# gyrotestbench.net
KiCad netlist of a schematic drawn in EAGLE
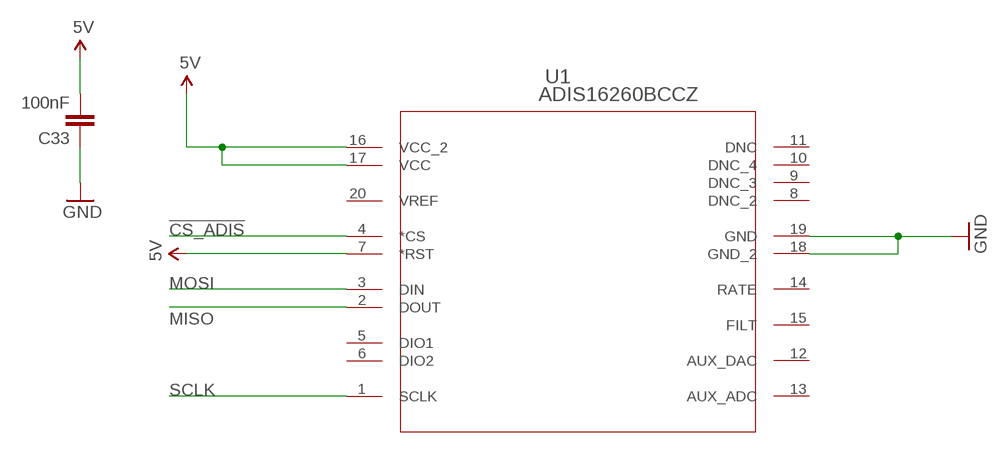
[diagram p0: schematic, sheet 1]
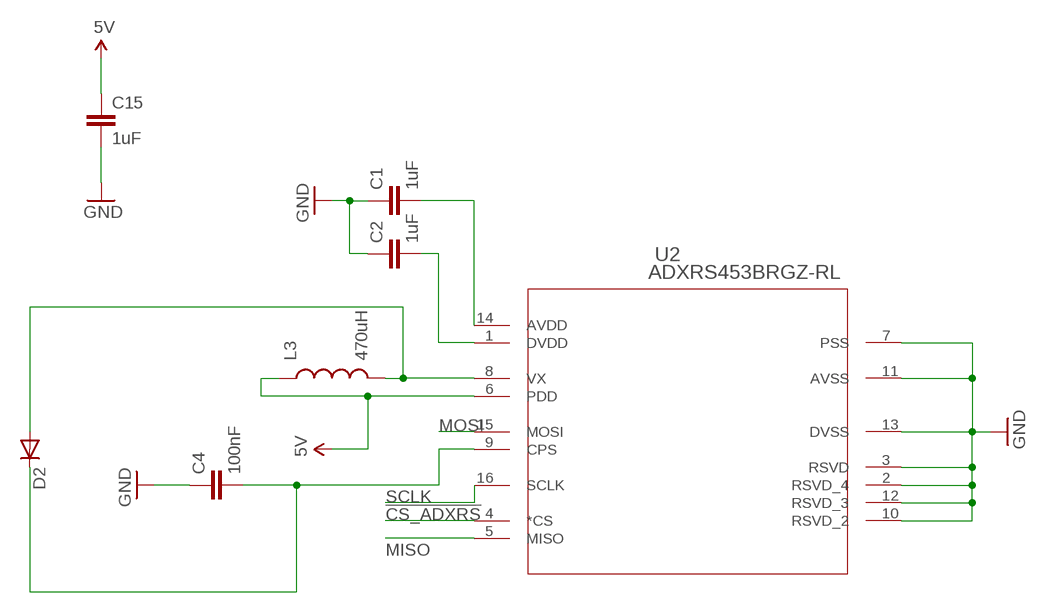
[diagram p1: schematic, sheet 2]
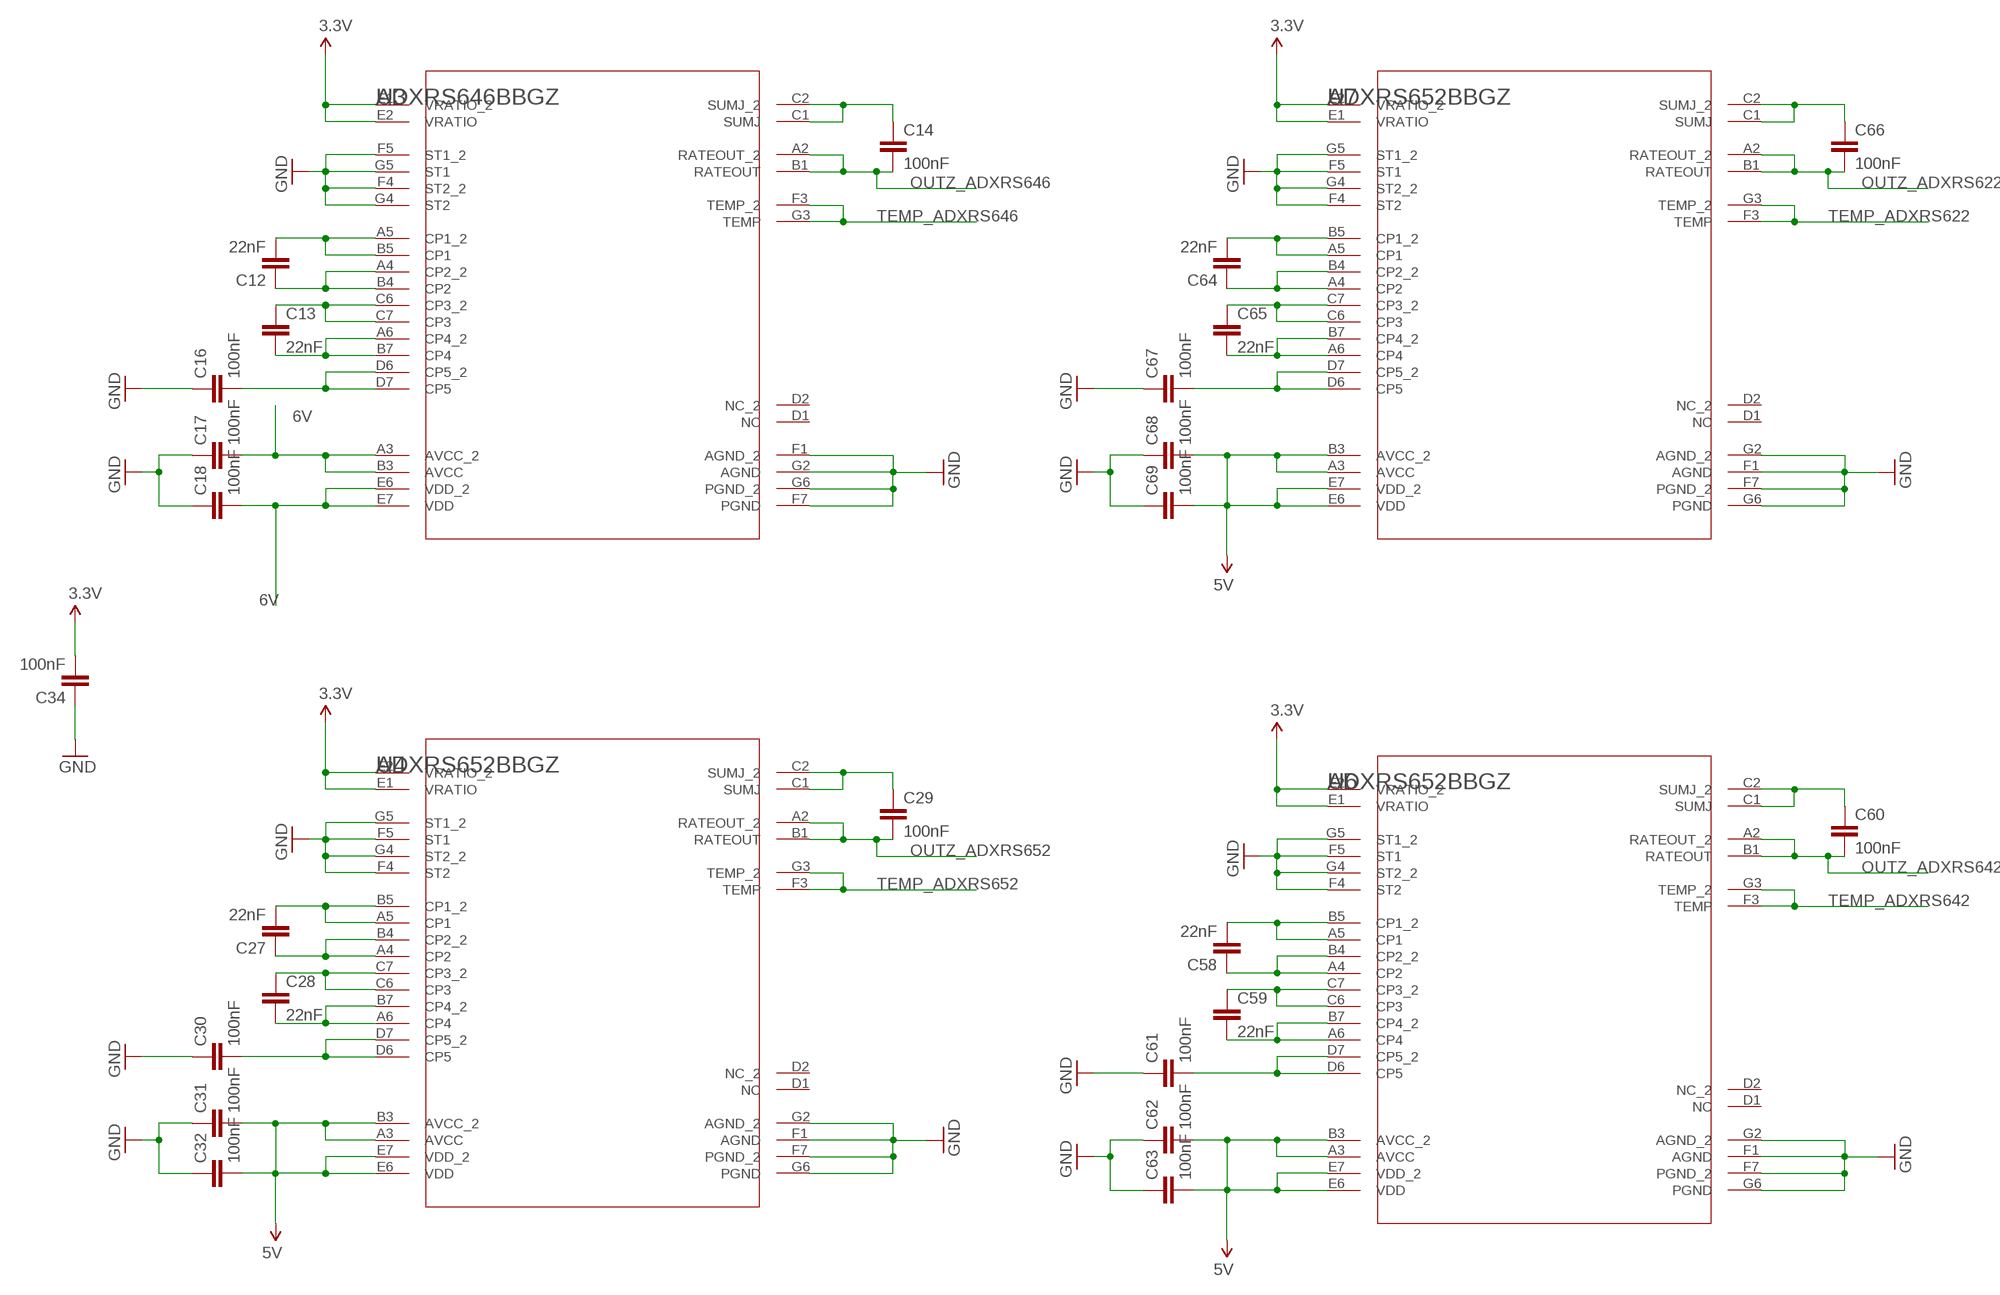
[diagram p2: schematic, sheet 3]
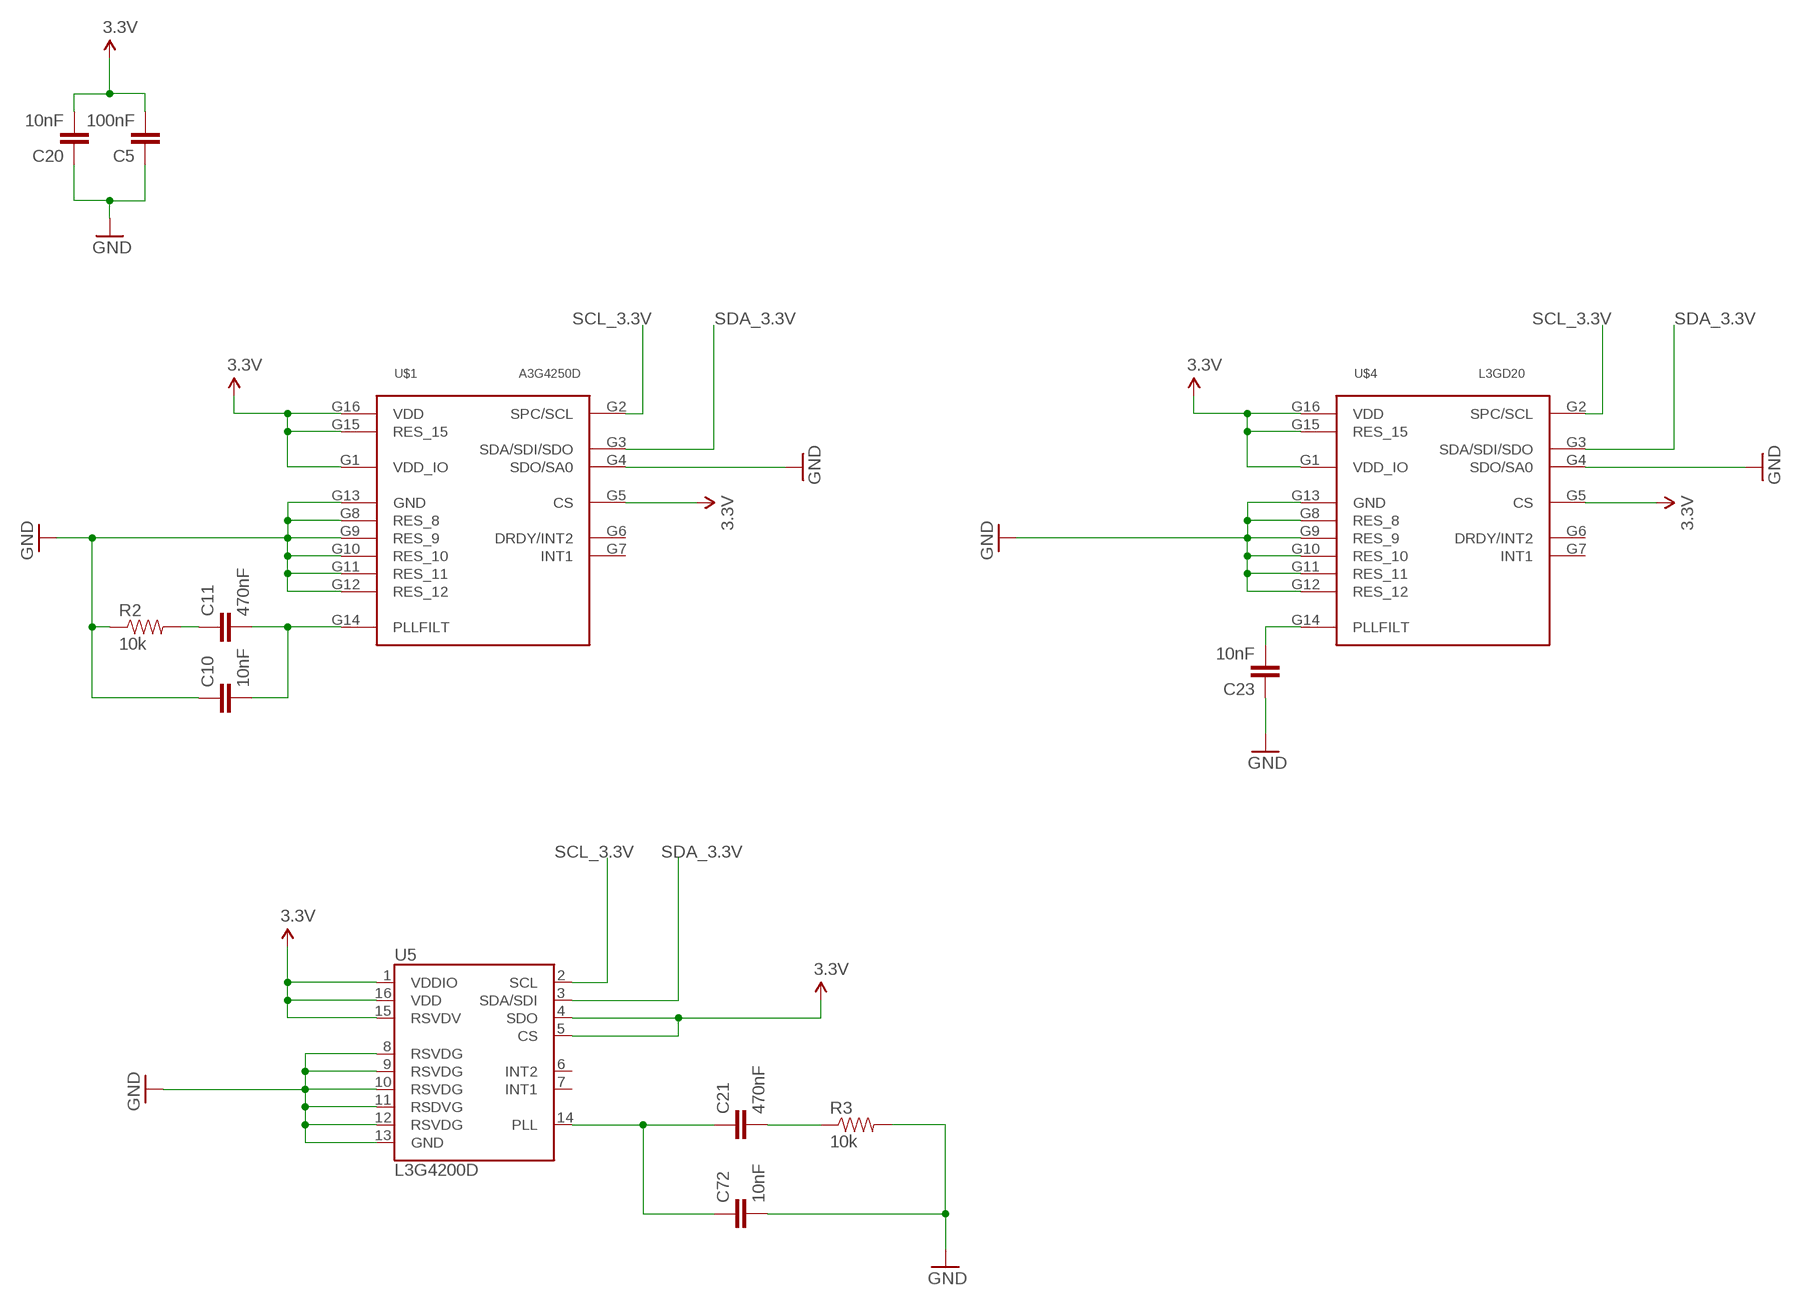
[diagram p3: schematic, sheet 4]
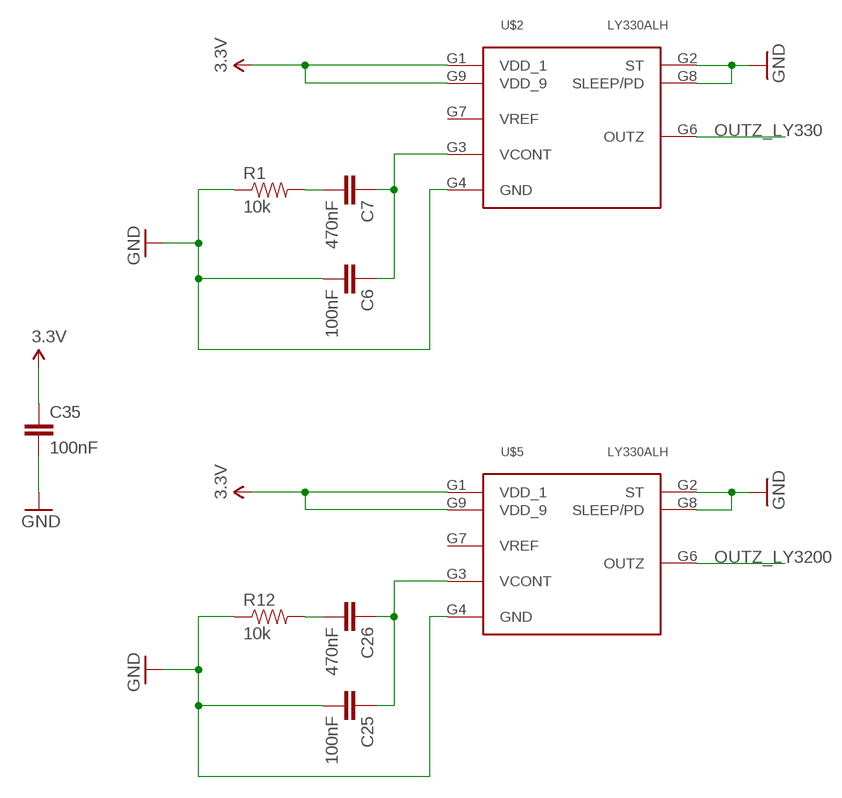
[diagram p4: schematic, sheet 5]
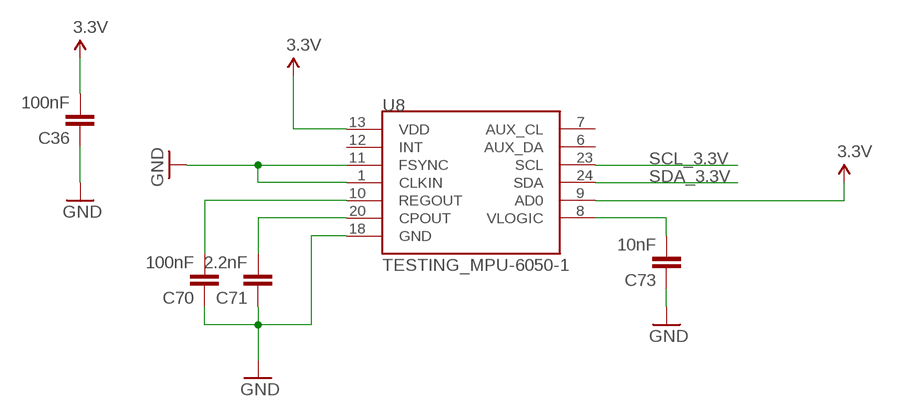
[diagram p5: schematic, sheet 6]
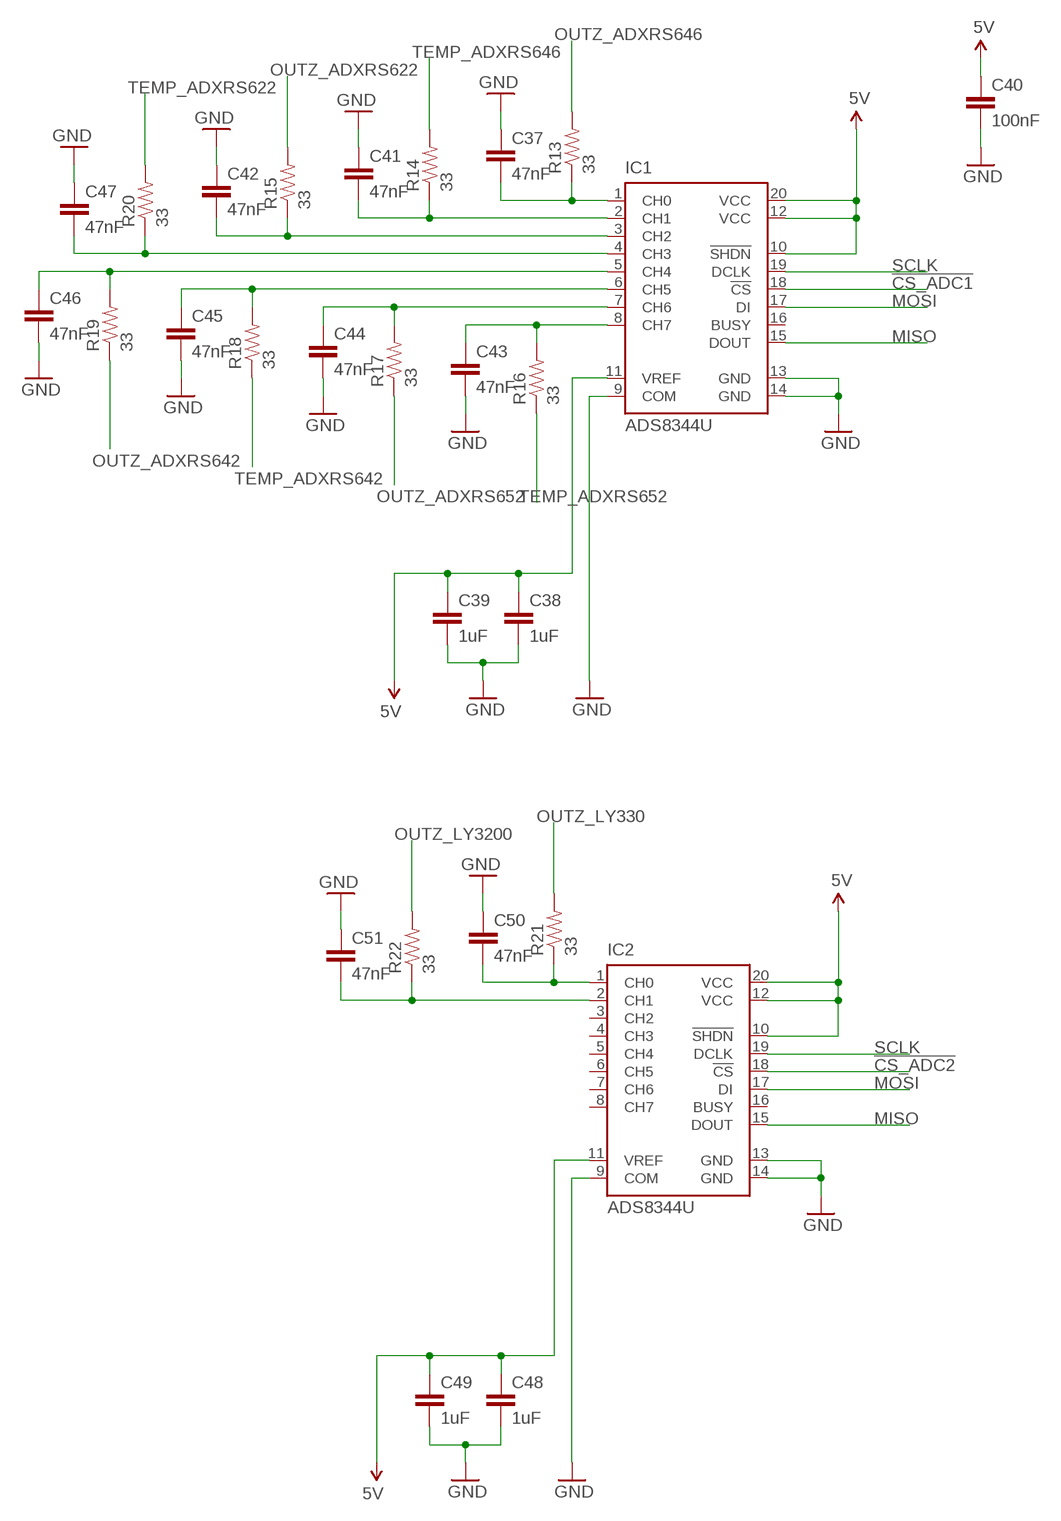
[diagram p6: schematic, sheet 7]
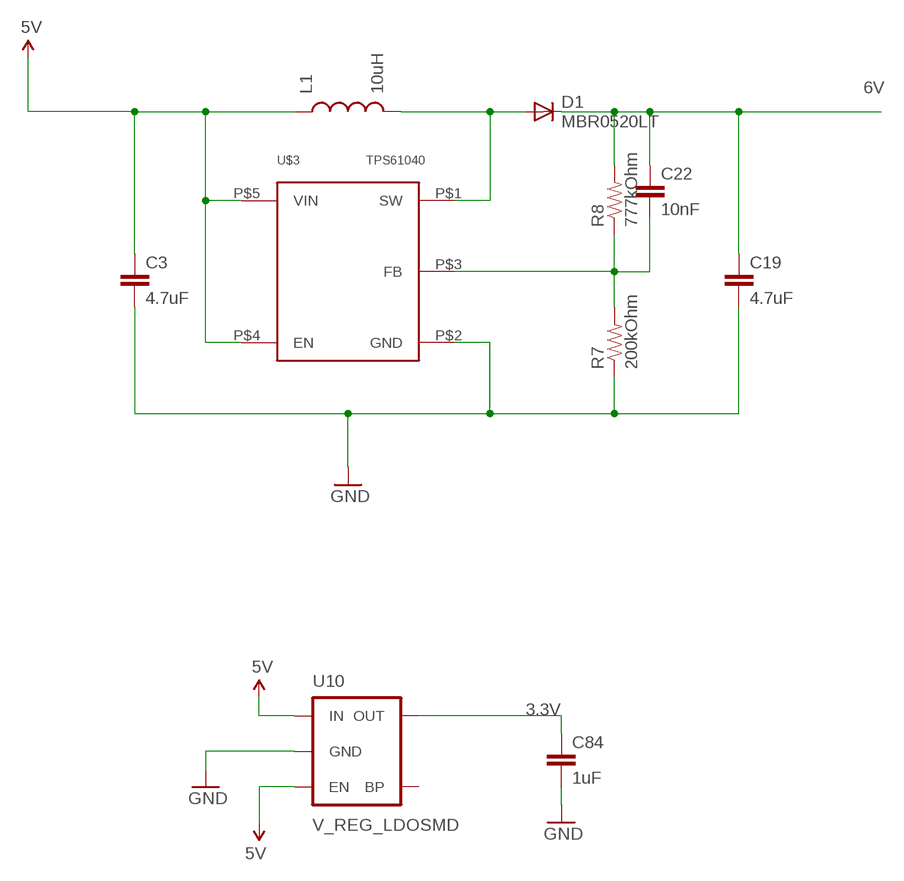
[diagram p7: schematic, sheet 8]
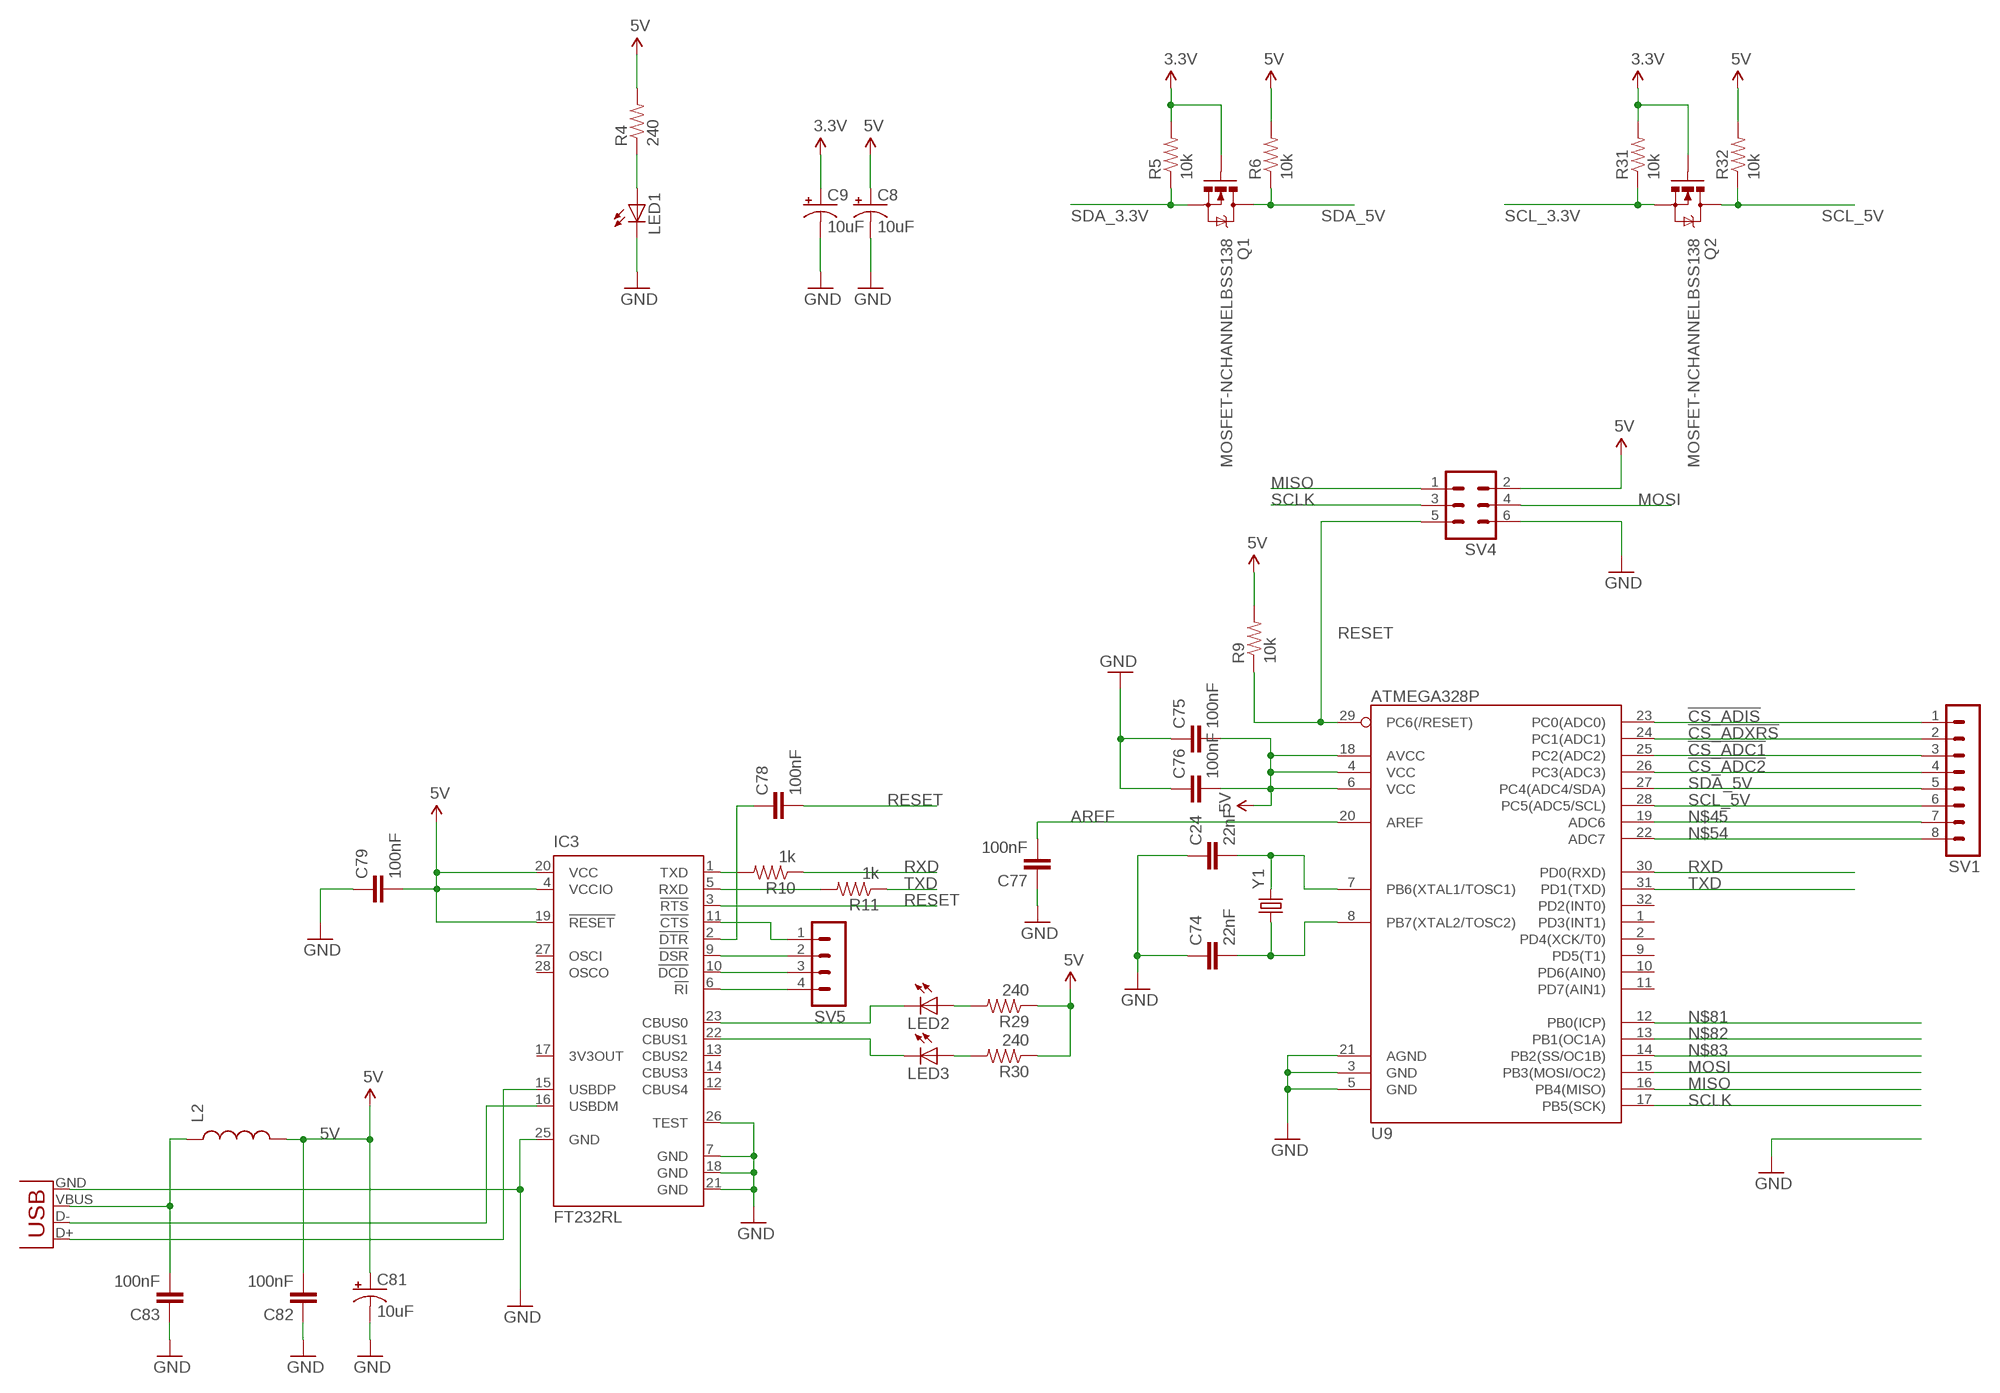
[diagram p8: schematic, sheet 9]

(export (version "E")
  (design (tool "Eeschema 10.0.6"))
  (components
    (comp (ref "C6")
      (value "100nF")
      (footprint "eagle-import:0603-CAP")
      (libsource (lib "eagle-import") (part "CAP0603-CAP"))
    )
    (comp (ref "C7")
      (value "470nF")
      (footprint "eagle-import:0603-CAP")
      (libsource (lib "eagle-import") (part "CAP0603-CAP"))
    )
    (comp (ref "C25")
      (value "100nF")
      (footprint "eagle-import:0603-CAP")
      (libsource (lib "eagle-import") (part "CAP0603-CAP"))
    )
    (comp (ref "C26")
      (value "470nF")
      (footprint "eagle-import:0603-CAP")
      (libsource (lib "eagle-import") (part "CAP0603-CAP"))
    )
    (comp (ref "C35")
      (value "100nF")
      (footprint "eagle-import:0603-CAP")
      (libsource (lib "eagle-import") (part "CAP0603-CAP"))
    )
    (comp (ref "R1")
      (value "10k")
      (footprint "eagle-import:0603-RES")
      (libsource (lib "eagle-import") (part "RESISTOR0603-RES"))
    )
    (comp (ref "R12")
      (value "10k")
      (footprint "eagle-import:0603-RES")
      (libsource (lib "eagle-import") (part "RESISTOR0603-RES"))
    )
    (comp (ref "U$2")
      (value "LY330ALH")
      (footprint "eagle-import:LGA-10")
      (libsource (lib "eagle-import") (part "LY330ALH"))
    )
    (comp (ref "U$5")
      (value "LY330ALH")
      (footprint "eagle-import:LGA-10")
      (libsource (lib "eagle-import") (part "LY330ALH"))
    )
    (comp (ref "C3")
      (value "4.7uF")
      (footprint "eagle-import:0603-CAP")
      (libsource (lib "eagle-import") (part "CAP0603-CAP"))
    )
    (comp (ref "C19")
      (value "4.7uF")
      (footprint "eagle-import:0603-CAP")
      (libsource (lib "eagle-import") (part "CAP0603-CAP"))
    )
    (comp (ref "C22")
      (value "10nF")
      (footprint "eagle-import:0603-CAP")
      (libsource (lib "eagle-import") (part "CAP0603-CAP"))
    )
    (comp (ref "C84")
      (value "1uF")
      (footprint "eagle-import:0603-CAP")
      (libsource (lib "eagle-import") (part "CAP0603-CAP"))
    )
    (comp (ref "D1")
      (value "MBR0520LT")
      (footprint "eagle-import:SOD123")
      (libsource (lib "eagle-import") (part "MBR0520LT"))
    )
    (comp (ref "L1")
      (value "10uH")
      (footprint "eagle-import:1210")
      (libsource (lib "eagle-import") (part "INDUCTOR1210"))
    )
    (comp (ref "R7")
      (value "200kOhm")
      (footprint "eagle-import:0603-RES")
      (libsource (lib "eagle-import") (part "RESISTOR0603-RES"))
    )
    (comp (ref "R8")
      (value "777kOhm")
      (footprint "eagle-import:0603-RES")
      (libsource (lib "eagle-import") (part "RESISTOR0603-RES"))
    )
    (comp (ref "U$3")
      (value "TPS61040")
      (footprint "eagle-import:DBV")
      (libsource (lib "eagle-import") (part "TPS61040"))
    )
    (comp (ref "U10")
      (value "V_REG_LDOSMD")
      (footprint "eagle-import:SOT23-5")
      (libsource (lib "eagle-import") (part "V_REG_LDOSMD"))
    )
    (comp (ref "C33")
      (value "100nF")
      (footprint "eagle-import:0603-CAP")
      (libsource (lib "eagle-import") (part "CAP0603-CAP"))
    )
    (comp (ref "U1")
      (value "ADIS16260BCCZ")
      (footprint "eagle-import:LGA_CC-20-1")
      (libsource (lib "eagle-import") (part "ADIS16260BCCZ"))
    )
    (comp (ref "C5")
      (value "100nF")
      (footprint "eagle-import:0603-CAP")
      (libsource (lib "eagle-import") (part "CAP0603-CAP"))
    )
    (comp (ref "C10")
      (value "10nF")
      (footprint "eagle-import:0603-CAP")
      (libsource (lib "eagle-import") (part "CAP0603-CAP"))
    )
    (comp (ref "C11")
      (value "470nF")
      (footprint "eagle-import:0603-CAP")
      (libsource (lib "eagle-import") (part "CAP0603-CAP"))
    )
    (comp (ref "C20")
      (value "10nF")
      (footprint "eagle-import:0603-CAP")
      (libsource (lib "eagle-import") (part "CAP0603-CAP"))
    )
    (comp (ref "C21")
      (value "470nF")
      (footprint "eagle-import:0603-CAP")
      (libsource (lib "eagle-import") (part "CAP0603-CAP"))
    )
    (comp (ref "C23")
      (value "10nF")
      (footprint "eagle-import:0603-CAP")
      (libsource (lib "eagle-import") (part "CAP0603-CAP"))
    )
    (comp (ref "C72")
      (value "10nF")
      (footprint "eagle-import:0603-CAP")
      (libsource (lib "eagle-import") (part "CAP0603-CAP"))
    )
    (comp (ref "R2")
      (value "10k")
      (footprint "eagle-import:0603-RES")
      (libsource (lib "eagle-import") (part "RESISTOR0603-RES"))
    )
    (comp (ref "R3")
      (value "10k")
      (footprint "eagle-import:0603-RES")
      (libsource (lib "eagle-import") (part "RESISTOR0603-RES"))
    )
    (comp (ref "U$1")
      (value "A3G4250D")
      (footprint "eagle-import:LGA-16")
      (libsource (lib "eagle-import") (part "A3G4250D"))
    )
    (comp (ref "U$4")
      (value "L3GD20")
      (footprint "eagle-import:LGA-16")
      (libsource (lib "eagle-import") (part "L3GD20"))
    )
    (comp (ref "U5")
      (value "L3G4200D")
      (footprint "eagle-import:LGA16-4X4")
      (libsource (lib "eagle-import") (part "L3G4200D"))
    )
    (comp (ref "C36")
      (value "100nF")
      (footprint "eagle-import:0603-CAP")
      (libsource (lib "eagle-import") (part "CAP0603-CAP"))
    )
    (comp (ref "C70")
      (value "100nF")
      (footprint "eagle-import:0603-CAP")
      (libsource (lib "eagle-import") (part "CAP0603-CAP"))
    )
    (comp (ref "C71")
      (value "2.2nF")
      (footprint "eagle-import:0603-CAP")
      (libsource (lib "eagle-import") (part "CAP0603-CAP"))
    )
    (comp (ref "C73")
      (value "10nF")
      (footprint "eagle-import:0603-CAP")
      (libsource (lib "eagle-import") (part "CAP0603-CAP"))
    )
    (comp (ref "U8")
      (value "TESTING_MPU-6050-1")
      (footprint "eagle-import:TESTING_QFN-24-4MM2")
      (libsource (lib "eagle-import") (part "TESTING_MPU-6050-1"))
    )
    (comp (ref "C12")
      (value "22nF")
      (footprint "eagle-import:0603-CAP")
      (libsource (lib "eagle-import") (part "CAP0603-CAP"))
    )
    (comp (ref "C13")
      (value "22nF")
      (footprint "eagle-import:0603-CAP")
      (libsource (lib "eagle-import") (part "CAP0603-CAP"))
    )
    (comp (ref "C14")
      (value "100nF")
      (footprint "eagle-import:0603-CAP")
      (libsource (lib "eagle-import") (part "CAP0603-CAP"))
    )
    (comp (ref "C16")
      (value "100nF")
      (footprint "eagle-import:0603-CAP")
      (libsource (lib "eagle-import") (part "CAP0603-CAP"))
    )
    (comp (ref "C17")
      (value "100nF")
      (footprint "eagle-import:0603-CAP")
      (libsource (lib "eagle-import") (part "CAP0603-CAP"))
    )
    (comp (ref "C18")
      (value "100nF")
      (footprint "eagle-import:0603-CAP")
      (libsource (lib "eagle-import") (part "CAP0603-CAP"))
    )
    (comp (ref "C27")
      (value "22nF")
      (footprint "eagle-import:0603-CAP")
      (libsource (lib "eagle-import") (part "CAP0603-CAP"))
    )
    (comp (ref "C28")
      (value "22nF")
      (footprint "eagle-import:0603-CAP")
      (libsource (lib "eagle-import") (part "CAP0603-CAP"))
    )
    (comp (ref "C29")
      (value "100nF")
      (footprint "eagle-import:0603-CAP")
      (libsource (lib "eagle-import") (part "CAP0603-CAP"))
    )
    (comp (ref "C30")
      (value "100nF")
      (footprint "eagle-import:0603-CAP")
      (libsource (lib "eagle-import") (part "CAP0603-CAP"))
    )
    (comp (ref "C31")
      (value "100nF")
      (footprint "eagle-import:0603-CAP")
      (libsource (lib "eagle-import") (part "CAP0603-CAP"))
    )
    (comp (ref "C32")
      (value "100nF")
      (footprint "eagle-import:0603-CAP")
      (libsource (lib "eagle-import") (part "CAP0603-CAP"))
    )
    (comp (ref "C34")
      (value "100nF")
      (footprint "eagle-import:0603-CAP")
      (libsource (lib "eagle-import") (part "CAP0603-CAP"))
    )
    (comp (ref "C58")
      (value "22nF")
      (footprint "eagle-import:0603-CAP")
      (libsource (lib "eagle-import") (part "CAP0603-CAP"))
    )
    (comp (ref "C59")
      (value "22nF")
      (footprint "eagle-import:0603-CAP")
      (libsource (lib "eagle-import") (part "CAP0603-CAP"))
    )
    (comp (ref "C60")
      (value "100nF")
      (footprint "eagle-import:0603-CAP")
      (libsource (lib "eagle-import") (part "CAP0603-CAP"))
    )
    (comp (ref "C61")
      (value "100nF")
      (footprint "eagle-import:0603-CAP")
      (libsource (lib "eagle-import") (part "CAP0603-CAP"))
    )
    (comp (ref "C62")
      (value "100nF")
      (footprint "eagle-import:0603-CAP")
      (libsource (lib "eagle-import") (part "CAP0603-CAP"))
    )
    (comp (ref "C63")
      (value "100nF")
      (footprint "eagle-import:0603-CAP")
      (libsource (lib "eagle-import") (part "CAP0603-CAP"))
    )
    (comp (ref "C64")
      (value "22nF")
      (footprint "eagle-import:0603-CAP")
      (libsource (lib "eagle-import") (part "CAP0603-CAP"))
    )
    (comp (ref "C65")
      (value "22nF")
      (footprint "eagle-import:0603-CAP")
      (libsource (lib "eagle-import") (part "CAP0603-CAP"))
    )
    (comp (ref "C66")
      (value "100nF")
      (footprint "eagle-import:0603-CAP")
      (libsource (lib "eagle-import") (part "CAP0603-CAP"))
    )
    (comp (ref "C67")
      (value "100nF")
      (footprint "eagle-import:0603-CAP")
      (libsource (lib "eagle-import") (part "CAP0603-CAP"))
    )
    (comp (ref "C68")
      (value "100nF")
      (footprint "eagle-import:0603-CAP")
      (libsource (lib "eagle-import") (part "CAP0603-CAP"))
    )
    (comp (ref "C69")
      (value "100nF")
      (footprint "eagle-import:0603-CAP")
      (libsource (lib "eagle-import") (part "CAP0603-CAP"))
    )
    (comp (ref "U3")
      (value "ADXRS646BBGZ")
      (footprint "eagle-import:BG_32_3")
      (fields (field (name "MANUFACTURER_PART_NUMBER") "ADXRS613BBGZ"))
      (libsource (lib "eagle-import") (part "ADXRS646BBGZ"))
    )
    (comp (ref "U4")
      (value "ADXRS652BBGZ")
      (footprint "eagle-import:BG_32_3")
      (libsource (lib "eagle-import") (part "ADXRS652BBGZ"))
    )
    (comp (ref "U6")
      (value "ADXRS652BBGZ")
      (footprint "eagle-import:BG_32_3")
      (libsource (lib "eagle-import") (part "ADXRS652BBGZ"))
    )
    (comp (ref "U7")
      (value "ADXRS652BBGZ")
      (footprint "eagle-import:BG_32_3")
      (libsource (lib "eagle-import") (part "ADXRS652BBGZ"))
    )
    (comp (ref "C8")
      (value "10uF")
      (footprint "eagle-import:PANASONIC_B")
      (libsource (lib "eagle-import") (part "CPOL-USB"))
    )
    (comp (ref "C9")
      (value "10uF")
      (footprint "eagle-import:PANASONIC_B")
      (libsource (lib "eagle-import") (part "CPOL-USB"))
    )
    (comp (ref "C24")
      (value "22nF")
      (footprint "eagle-import:0603-CAP")
      (libsource (lib "eagle-import") (part "CAP0603-CAP"))
    )
    (comp (ref "C74")
      (value "22nF")
      (footprint "eagle-import:0603-CAP")
      (libsource (lib "eagle-import") (part "CAP0603-CAP"))
    )
    (comp (ref "C75")
      (value "100nF")
      (footprint "eagle-import:0603-CAP")
      (libsource (lib "eagle-import") (part "CAP0603-CAP"))
    )
    (comp (ref "C76")
      (value "100nF")
      (footprint "eagle-import:0603-CAP")
      (libsource (lib "eagle-import") (part "CAP0603-CAP"))
    )
    (comp (ref "C77")
      (value "100nF")
      (footprint "eagle-import:0603-CAP")
      (libsource (lib "eagle-import") (part "CAP0603-CAP"))
    )
    (comp (ref "C78")
      (value "100nF")
      (footprint "eagle-import:0603-CAP")
      (libsource (lib "eagle-import") (part "CAP0603-CAP"))
    )
    (comp (ref "C79")
      (value "100nF")
      (footprint "eagle-import:0603-CAP")
      (libsource (lib "eagle-import") (part "CAP0603-CAP"))
    )
    (comp (ref "C81")
      (value "10uF")
      (footprint "eagle-import:PANASONIC_B")
      (libsource (lib "eagle-import") (part "CPOL-USB"))
    )
    (comp (ref "C82")
      (value "100nF")
      (footprint "eagle-import:0603-CAP")
      (libsource (lib "eagle-import") (part "CAP0603-CAP"))
    )
    (comp (ref "C83")
      (value "100nF")
      (footprint "eagle-import:0603-CAP")
      (libsource (lib "eagle-import") (part "CAP0603-CAP"))
    )
    (comp (ref "IC3")
      (value "FT232RL")
      (footprint "eagle-import:SSOP28")
      (libsource (lib "eagle-import") (part "FT232RL"))
    )
    (comp (ref "JP1")
      (value "USBSMD")
      (footprint "eagle-import:USB-MINIB")
      (libsource (lib "eagle-import") (part "USBSMD"))
    )
    (comp (ref "L2")
      (value "INDUCTOR0603")
      (footprint "eagle-import:0603")
      (libsource (lib "eagle-import") (part "INDUCTOR0603"))
    )
    (comp (ref "LED1")
      (value "LED0603")
      (footprint "eagle-import:LED-0603")
      (libsource (lib "eagle-import") (part "LED0603"))
    )
    (comp (ref "LED2")
      (value "LED0603")
      (footprint "eagle-import:LED-0603")
      (libsource (lib "eagle-import") (part "LED0603"))
    )
    (comp (ref "LED3")
      (value "LED0603")
      (footprint "eagle-import:LED-0603")
      (libsource (lib "eagle-import") (part "LED0603"))
    )
    (comp (ref "Q1")
      (value "MOSFET-NCHANNELBSS138")
      (footprint "eagle-import:SOT23")
      (libsource (lib "eagle-import") (part "MOSFET-NCHANNELBSS138"))
    )
    (comp (ref "Q2")
      (value "MOSFET-NCHANNELBSS138")
      (footprint "eagle-import:SOT23")
      (libsource (lib "eagle-import") (part "MOSFET-NCHANNELBSS138"))
    )
    (comp (ref "R4")
      (value "240")
      (footprint "eagle-import:0603-RES")
      (libsource (lib "eagle-import") (part "RESISTOR0603-RES"))
    )
    (comp (ref "R5")
      (value "10k")
      (footprint "eagle-import:0603-RES")
      (libsource (lib "eagle-import") (part "RESISTOR0603-RES"))
    )
    (comp (ref "R6")
      (value "10k")
      (footprint "eagle-import:0603-RES")
      (libsource (lib "eagle-import") (part "RESISTOR0603-RES"))
    )
    (comp (ref "R9")
      (value "10k")
      (footprint "eagle-import:0603-RES")
      (libsource (lib "eagle-import") (part "RESISTOR0603-RES"))
    )
    (comp (ref "R10")
      (value "1k")
      (footprint "eagle-import:0603-RES")
      (libsource (lib "eagle-import") (part "RESISTOR0603-RES"))
    )
    (comp (ref "R11")
      (value "1k")
      (footprint "eagle-import:0603-RES")
      (libsource (lib "eagle-import") (part "RESISTOR0603-RES"))
    )
    (comp (ref "R29")
      (value "240")
      (footprint "eagle-import:0603-RES")
      (libsource (lib "eagle-import") (part "RESISTOR0603-RES"))
    )
    (comp (ref "R30")
      (value "240")
      (footprint "eagle-import:0603-RES")
      (libsource (lib "eagle-import") (part "RESISTOR0603-RES"))
    )
    (comp (ref "R31")
      (value "10k")
      (footprint "eagle-import:0603-RES")
      (libsource (lib "eagle-import") (part "RESISTOR0603-RES"))
    )
    (comp (ref "R32")
      (value "10k")
      (footprint "eagle-import:0603-RES")
      (libsource (lib "eagle-import") (part "RESISTOR0603-RES"))
    )
    (comp (ref "SV1")
      (value "MA08-1")
      (footprint "eagle-import:MA08-1")
      (libsource (lib "eagle-import") (part "MA08-1"))
    )
    (comp (ref "SV4")
      (value "MA03-2")
      (footprint "eagle-import:MA03-2")
      (libsource (lib "eagle-import") (part "MA03-2"))
    )
    (comp (ref "SV5")
      (value "MA04-1")
      (footprint "eagle-import:MA04-1")
      (libsource (lib "eagle-import") (part "MA04-1"))
    )
    (comp (ref "U9")
      (value "ATMEGA328P")
      (footprint "eagle-import:TQFP32-08")
      (libsource (lib "eagle-import") (part "ATMEGA328_SMT"))
    )
    (comp (ref "Y1")
      (value "CRYSTALHC49US")
      (footprint "eagle-import:HC49US")
      (libsource (lib "eagle-import") (part "CRYSTALHC49US"))
    )
    (comp (ref "C1")
      (value "1uF")
      (footprint "eagle-import:0603-CAP")
      (libsource (lib "eagle-import") (part "CAP0603-CAP"))
    )
    (comp (ref "C2")
      (value "1uF")
      (footprint "eagle-import:0603-CAP")
      (libsource (lib "eagle-import") (part "CAP0603-CAP"))
    )
    (comp (ref "C4")
      (value "100nF")
      (footprint "eagle-import:0603-CAP")
      (libsource (lib "eagle-import") (part "CAP0603-CAP"))
    )
    (comp (ref "C15")
      (value "1uF")
      (footprint "eagle-import:0603-CAP")
      (libsource (lib "eagle-import") (part "CAP0603-CAP"))
    )
    (comp (ref "D2")
      (value "DIODEPTH")
      (footprint "eagle-import:DIODE-1N4001")
      (libsource (lib "eagle-import") (part "DIODEPTH"))
    )
    (comp (ref "L3")
      (value "470uH")
      (footprint "eagle-import:1210")
      (libsource (lib "eagle-import") (part "INDUCTOR1210"))
    )
    (comp (ref "U2")
      (value "ADXRS453BRGZ-RL")
      (footprint "eagle-import:RG_16_1")
      (libsource (lib "eagle-import") (part "ADXRS453BRGZ-RL"))
    )
    (comp (ref "C37")
      (value "47nF")
      (footprint "eagle-import:0603-CAP")
      (libsource (lib "eagle-import") (part "CAP0603-CAP"))
    )
    (comp (ref "C38")
      (value "1uF")
      (footprint "eagle-import:0603-CAP")
      (libsource (lib "eagle-import") (part "CAP0603-CAP"))
    )
    (comp (ref "C39")
      (value "1uF")
      (footprint "eagle-import:0603-CAP")
      (libsource (lib "eagle-import") (part "CAP0603-CAP"))
    )
    (comp (ref "C40")
      (value "100nF")
      (footprint "eagle-import:0603-CAP")
      (libsource (lib "eagle-import") (part "CAP0603-CAP"))
    )
    (comp (ref "C41")
      (value "47nF")
      (footprint "eagle-import:0603-CAP")
      (libsource (lib "eagle-import") (part "CAP0603-CAP"))
    )
    (comp (ref "C42")
      (value "47nF")
      (footprint "eagle-import:0603-CAP")
      (libsource (lib "eagle-import") (part "CAP0603-CAP"))
    )
    (comp (ref "C43")
      (value "47nF")
      (footprint "eagle-import:0603-CAP")
      (libsource (lib "eagle-import") (part "CAP0603-CAP"))
    )
    (comp (ref "C44")
      (value "47nF")
      (footprint "eagle-import:0603-CAP")
      (libsource (lib "eagle-import") (part "CAP0603-CAP"))
    )
    (comp (ref "C45")
      (value "47nF")
      (footprint "eagle-import:0603-CAP")
      (libsource (lib "eagle-import") (part "CAP0603-CAP"))
    )
    (comp (ref "C46")
      (value "47nF")
      (footprint "eagle-import:0603-CAP")
      (libsource (lib "eagle-import") (part "CAP0603-CAP"))
    )
    (comp (ref "C47")
      (value "47nF")
      (footprint "eagle-import:0603-CAP")
      (libsource (lib "eagle-import") (part "CAP0603-CAP"))
    )
    (comp (ref "C48")
      (value "1uF")
      (footprint "eagle-import:0603-CAP")
      (libsource (lib "eagle-import") (part "CAP0603-CAP"))
    )
    (comp (ref "C49")
      (value "1uF")
      (footprint "eagle-import:0603-CAP")
      (libsource (lib "eagle-import") (part "CAP0603-CAP"))
    )
    (comp (ref "C50")
      (value "47nF")
      (footprint "eagle-import:0603-CAP")
      (libsource (lib "eagle-import") (part "CAP0603-CAP"))
    )
    (comp (ref "C51")
      (value "47nF")
      (footprint "eagle-import:0603-CAP")
      (libsource (lib "eagle-import") (part "CAP0603-CAP"))
    )
    (comp (ref "IC1")
      (value "ADS8344U")
      (footprint "eagle-import:SSOP20BU")
      (fields (field (name "MPN") "ADS8344NB"))
      (libsource (lib "eagle-import") (part "ADS8344U"))
    )
    (comp (ref "IC2")
      (value "ADS8344U")
      (footprint "eagle-import:SSOP20BU")
      (fields (field (name "MPN") "ADS8344NB"))
      (libsource (lib "eagle-import") (part "ADS8344U"))
    )
    (comp (ref "R13")
      (value "33")
      (footprint "eagle-import:0603-RES")
      (libsource (lib "eagle-import") (part "RESISTOR0603-RES"))
    )
    (comp (ref "R14")
      (value "33")
      (footprint "eagle-import:0603-RES")
      (libsource (lib "eagle-import") (part "RESISTOR0603-RES"))
    )
    (comp (ref "R15")
      (value "33")
      (footprint "eagle-import:0603-RES")
      (libsource (lib "eagle-import") (part "RESISTOR0603-RES"))
    )
    (comp (ref "R16")
      (value "33")
      (footprint "eagle-import:0603-RES")
      (libsource (lib "eagle-import") (part "RESISTOR0603-RES"))
    )
    (comp (ref "R17")
      (value "33")
      (footprint "eagle-import:0603-RES")
      (libsource (lib "eagle-import") (part "RESISTOR0603-RES"))
    )
    (comp (ref "R18")
      (value "33")
      (footprint "eagle-import:0603-RES")
      (libsource (lib "eagle-import") (part "RESISTOR0603-RES"))
    )
    (comp (ref "R19")
      (value "33")
      (footprint "eagle-import:0603-RES")
      (libsource (lib "eagle-import") (part "RESISTOR0603-RES"))
    )
    (comp (ref "R20")
      (value "33")
      (footprint "eagle-import:0603-RES")
      (libsource (lib "eagle-import") (part "RESISTOR0603-RES"))
    )
    (comp (ref "R21")
      (value "33")
      (footprint "eagle-import:0603-RES")
      (libsource (lib "eagle-import") (part "RESISTOR0603-RES"))
    )
    (comp (ref "R22")
      (value "33")
      (footprint "eagle-import:0603-RES")
      (libsource (lib "eagle-import") (part "RESISTOR0603-RES"))
    )
  )
  (nets
    (net (code "1") (name "3.3V") (class "Default")
      (node (ref "C20") (pin "2") (pinfunction "2_2") (pintype "passive"))
      (node (ref "C34") (pin "2") (pinfunction "2_2") (pintype "passive"))
      (node (ref "C35") (pin "1") (pinfunction "1_1") (pintype "passive"))
      (node (ref "C36") (pin "2") (pinfunction "2_2") (pintype "passive"))
      (node (ref "C5") (pin "2") (pinfunction "2_2") (pintype "passive"))
      (node (ref "C84") (pin "1") (pinfunction "1_1") (pintype "passive"))
      (node (ref "C9") (pin "+") (pinfunction "+_+") (pintype "passive"))
      (node (ref "Q1") (pin "1") (pinfunction "G_1") (pintype "passive"))
      (node (ref "Q2") (pin "1") (pinfunction "G_1") (pintype "passive"))
      (node (ref "R31") (pin "2") (pinfunction "2_2") (pintype "passive"))
      (node (ref "R5") (pin "2") (pinfunction "2_2") (pintype "passive"))
      (node (ref "U$1") (pin "G1") (pinfunction "VDD_IO_G1") (pintype "bidirectional"))
      (node (ref "U$1") (pin "G15") (pinfunction "RES_15_G15") (pintype "bidirectional"))
      (node (ref "U$1") (pin "G16") (pinfunction "VDD_G16") (pintype "bidirectional"))
      (node (ref "U$1") (pin "G5") (pinfunction "CS_G5") (pintype "bidirectional"))
      (node (ref "U$2") (pin "G1") (pinfunction "VDD_1_G1") (pintype "bidirectional"))
      (node (ref "U$2") (pin "G9") (pinfunction "VDD_9_G9") (pintype "bidirectional"))
      (node (ref "U$4") (pin "G1") (pinfunction "VDD_IO_G1") (pintype "bidirectional"))
      (node (ref "U$4") (pin "G15") (pinfunction "RES_15_G15") (pintype "bidirectional"))
      (node (ref "U$4") (pin "G16") (pinfunction "VDD_G16") (pintype "bidirectional"))
      (node (ref "U$4") (pin "G5") (pinfunction "CS_G5") (pintype "bidirectional"))
      (node (ref "U$5") (pin "G1") (pinfunction "VDD_1_G1") (pintype "bidirectional"))
      (node (ref "U$5") (pin "G9") (pinfunction "VDD_9_G9") (pintype "bidirectional"))
      (node (ref "U10") (pin "5") (pinfunction "OUT_5") (pintype "passive"))
      (node (ref "U3") (pin "E1") (pinfunction "VRATIO_2_E1") (pintype "power_in"))
      (node (ref "U3") (pin "E2") (pinfunction "VRATIO_E2") (pintype "power_in"))
      (node (ref "U4") (pin "E1") (pinfunction "VRATIO_E1") (pintype "power_in"))
      (node (ref "U4") (pin "E2") (pinfunction "VRATIO_2_E2") (pintype "power_in"))
      (node (ref "U5") (pin "1") (pinfunction "VDDIO_1") (pintype "bidirectional"))
      (node (ref "U5") (pin "15") (pinfunction "RSVDV_15") (pintype "bidirectional"))
      (node (ref "U5") (pin "16") (pinfunction "VDD_16") (pintype "bidirectional"))
      (node (ref "U5") (pin "4") (pinfunction "SDO_4") (pintype "bidirectional"))
      (node (ref "U5") (pin "5") (pinfunction "CS_5") (pintype "bidirectional"))
      (node (ref "U6") (pin "E1") (pinfunction "VRATIO_E1") (pintype "power_in"))
      (node (ref "U6") (pin "E2") (pinfunction "VRATIO_2_E2") (pintype "power_in"))
      (node (ref "U7") (pin "E1") (pinfunction "VRATIO_E1") (pintype "power_in"))
      (node (ref "U7") (pin "E2") (pinfunction "VRATIO_2_E2") (pintype "power_in"))
      (node (ref "U8") (pin "13") (pinfunction "VDD_13") (pintype "bidirectional"))
      (node (ref "U8") (pin "9") (pinfunction "AD0_9") (pintype "bidirectional"))
    )
    (net (code "2") (name "5V") (class "Default")
      (node (ref "C15") (pin "1") (pinfunction "1_1") (pintype "passive"))
      (node (ref "C3") (pin "1") (pinfunction "1_1") (pintype "passive"))
      (node (ref "C31") (pin "2") (pinfunction "2_2") (pintype "passive"))
      (node (ref "C32") (pin "2") (pinfunction "2_2") (pintype "passive"))
      (node (ref "C33") (pin "2") (pinfunction "2_2") (pintype "passive"))
      (node (ref "C38") (pin "1") (pinfunction "1_1") (pintype "passive"))
      (node (ref "C39") (pin "1") (pinfunction "1_1") (pintype "passive"))
      (node (ref "C40") (pin "1") (pinfunction "1_1") (pintype "passive"))
      (node (ref "C48") (pin "1") (pinfunction "1_1") (pintype "passive"))
      (node (ref "C49") (pin "1") (pinfunction "1_1") (pintype "passive"))
      (node (ref "C62") (pin "2") (pinfunction "2_2") (pintype "passive"))
      (node (ref "C63") (pin "2") (pinfunction "2_2") (pintype "passive"))
      (node (ref "C68") (pin "2") (pinfunction "2_2") (pintype "passive"))
      (node (ref "C69") (pin "2") (pinfunction "2_2") (pintype "passive"))
      (node (ref "C75") (pin "2") (pinfunction "2_2") (pintype "passive"))
      (node (ref "C76") (pin "2") (pinfunction "2_2") (pintype "passive"))
      (node (ref "C79") (pin "2") (pinfunction "2_2") (pintype "passive"))
      (node (ref "C8") (pin "+") (pinfunction "+_+") (pintype "passive"))
      (node (ref "C81") (pin "+") (pinfunction "+_+") (pintype "passive"))
      (node (ref "C82") (pin "2") (pinfunction "2_2") (pintype "passive"))
      (node (ref "IC1") (pin "10") (pinfunction "~{SHDN}_10") (pintype "input"))
      (node (ref "IC1") (pin "11") (pinfunction "VREF_11") (pintype "input"))
      (node (ref "IC1") (pin "12") (pinfunction "VCC_12") (pintype "power_in"))
      (node (ref "IC1") (pin "20") (pinfunction "VCC_20") (pintype "power_in"))
      (node (ref "IC2") (pin "10") (pinfunction "~{SHDN}_10") (pintype "input"))
      (node (ref "IC2") (pin "11") (pinfunction "VREF_11") (pintype "input"))
      (node (ref "IC2") (pin "12") (pinfunction "VCC_12") (pintype "power_in"))
      (node (ref "IC2") (pin "20") (pinfunction "VCC_20") (pintype "power_in"))
      (node (ref "IC3") (pin "19") (pinfunction "~{RESET}_19") (pintype "input"))
      (node (ref "IC3") (pin "20") (pinfunction "VCC_20") (pintype "power_in"))
      (node (ref "IC3") (pin "4") (pinfunction "VCCIO_4") (pintype "power_in"))
      (node (ref "L1") (pin "1") (pinfunction "1_1") (pintype "passive"))
      (node (ref "L2") (pin "2") (pinfunction "2_2") (pintype "passive"))
      (node (ref "L3") (pin "1") (pinfunction "1_1") (pintype "passive"))
      (node (ref "R29") (pin "1") (pinfunction "1_1") (pintype "passive"))
      (node (ref "R30") (pin "1") (pinfunction "1_1") (pintype "passive"))
      (node (ref "R32") (pin "2") (pinfunction "2_2") (pintype "passive"))
      (node (ref "R4") (pin "2") (pinfunction "2_2") (pintype "passive"))
      (node (ref "R6") (pin "2") (pinfunction "2_2") (pintype "passive"))
      (node (ref "R9") (pin "2") (pinfunction "2_2") (pintype "passive"))
      (node (ref "SV4") (pin "2") (pinfunction "2_2") (pintype "passive"))
      (node (ref "U$3") (pin "P$4") (pinfunction "EN_P$4") (pintype "bidirectional"))
      (node (ref "U$3") (pin "P$5") (pinfunction "VIN_P$5") (pintype "bidirectional"))
      (node (ref "U1") (pin "16") (pinfunction "VCC_2_16") (pintype "passive"))
      (node (ref "U1") (pin "17") (pinfunction "VCC_17") (pintype "passive"))
      (node (ref "U1") (pin "7") (pinfunction "*RST_7") (pintype "passive"))
      (node (ref "U10") (pin "1") (pinfunction "IN_1") (pintype "input"))
      (node (ref "U10") (pin "3") (pinfunction "EN_3") (pintype "input"))
      (node (ref "U2") (pin "6") (pinfunction "PDD_6") (pintype "passive"))
      (node (ref "U4") (pin "A3") (pinfunction "AVCC_A3") (pintype "power_in"))
      (node (ref "U4") (pin "B3") (pinfunction "AVCC_2_B3") (pintype "power_in"))
      (node (ref "U4") (pin "E6") (pinfunction "VDD_E6") (pintype "power_in"))
      (node (ref "U4") (pin "E7") (pinfunction "VDD_2_E7") (pintype "power_in"))
      (node (ref "U6") (pin "A3") (pinfunction "AVCC_A3") (pintype "power_in"))
      (node (ref "U6") (pin "B3") (pinfunction "AVCC_2_B3") (pintype "power_in"))
      (node (ref "U6") (pin "E6") (pinfunction "VDD_E6") (pintype "power_in"))
      (node (ref "U6") (pin "E7") (pinfunction "VDD_2_E7") (pintype "power_in"))
      (node (ref "U7") (pin "A3") (pinfunction "AVCC_A3") (pintype "power_in"))
      (node (ref "U7") (pin "B3") (pinfunction "AVCC_2_B3") (pintype "power_in"))
      (node (ref "U7") (pin "E6") (pinfunction "VDD_E6") (pintype "power_in"))
      (node (ref "U7") (pin "E7") (pinfunction "VDD_2_E7") (pintype "power_in"))
      (node (ref "U9") (pin "18") (pinfunction "AVCC_18") (pintype "bidirectional"))
      (node (ref "U9") (pin "4") (pinfunction "VCC_4") (pintype "bidirectional"))
      (node (ref "U9") (pin "6") (pinfunction "VCC_6") (pintype "bidirectional"))
    )
    (net (code "3") (name "6V") (class "Default")
      (node (ref "C17") (pin "2") (pinfunction "2_2") (pintype "passive"))
      (node (ref "C18") (pin "2") (pinfunction "2_2") (pintype "passive"))
      (node (ref "C19") (pin "1") (pinfunction "1_1") (pintype "passive"))
      (node (ref "C22") (pin "1") (pinfunction "1_1") (pintype "passive"))
      (node (ref "D1") (pin "C") (pinfunction "C_C") (pintype "passive"))
      (node (ref "R8") (pin "2") (pinfunction "2_2") (pintype "passive"))
      (node (ref "U3") (pin "A3") (pinfunction "AVCC_2_A3") (pintype "power_in"))
      (node (ref "U3") (pin "B3") (pinfunction "AVCC_B3") (pintype "power_in"))
      (node (ref "U3") (pin "E6") (pinfunction "VDD_2_E6") (pintype "power_in"))
      (node (ref "U3") (pin "E7") (pinfunction "VDD_E7") (pintype "power_in"))
    )
    (net (code "4") (name "AREF") (class "Default")
      (node (ref "C77") (pin "2") (pinfunction "2_2") (pintype "passive"))
      (node (ref "U9") (pin "20") (pinfunction "AREF_20") (pintype "bidirectional"))
    )
    (net (code "5") (name "GND") (class "Default")
      (node (ref "C1") (pin "1") (pinfunction "1_1") (pintype "passive"))
      (node (ref "C10") (pin "1") (pinfunction "1_1") (pintype "passive"))
      (node (ref "C15") (pin "2") (pinfunction "2_2") (pintype "passive"))
      (node (ref "C16") (pin "1") (pinfunction "1_1") (pintype "passive"))
      (node (ref "C17") (pin "1") (pinfunction "1_1") (pintype "passive"))
      (node (ref "C18") (pin "1") (pinfunction "1_1") (pintype "passive"))
      (node (ref "C19") (pin "2") (pinfunction "2_2") (pintype "passive"))
      (node (ref "C2") (pin "1") (pinfunction "1_1") (pintype "passive"))
      (node (ref "C20") (pin "1") (pinfunction "1_1") (pintype "passive"))
      (node (ref "C23") (pin "1") (pinfunction "1_1") (pintype "passive"))
      (node (ref "C24") (pin "1") (pinfunction "1_1") (pintype "passive"))
      (node (ref "C25") (pin "2") (pinfunction "2_2") (pintype "passive"))
      (node (ref "C3") (pin "2") (pinfunction "2_2") (pintype "passive"))
      (node (ref "C30") (pin "1") (pinfunction "1_1") (pintype "passive"))
      (node (ref "C31") (pin "1") (pinfunction "1_1") (pintype "passive"))
      (node (ref "C32") (pin "1") (pinfunction "1_1") (pintype "passive"))
      (node (ref "C33") (pin "1") (pinfunction "1_1") (pintype "passive"))
      (node (ref "C34") (pin "1") (pinfunction "1_1") (pintype "passive"))
      (node (ref "C35") (pin "2") (pinfunction "2_2") (pintype "passive"))
      (node (ref "C36") (pin "1") (pinfunction "1_1") (pintype "passive"))
      (node (ref "C37") (pin "1") (pinfunction "1_1") (pintype "passive"))
      (node (ref "C38") (pin "2") (pinfunction "2_2") (pintype "passive"))
      (node (ref "C39") (pin "2") (pinfunction "2_2") (pintype "passive"))
      (node (ref "C4") (pin "1") (pinfunction "1_1") (pintype "passive"))
      (node (ref "C40") (pin "2") (pinfunction "2_2") (pintype "passive"))
      (node (ref "C41") (pin "1") (pinfunction "1_1") (pintype "passive"))
      (node (ref "C42") (pin "1") (pinfunction "1_1") (pintype "passive"))
      (node (ref "C43") (pin "2") (pinfunction "2_2") (pintype "passive"))
      (node (ref "C44") (pin "2") (pinfunction "2_2") (pintype "passive"))
      (node (ref "C45") (pin "2") (pinfunction "2_2") (pintype "passive"))
      (node (ref "C46") (pin "2") (pinfunction "2_2") (pintype "passive"))
      (node (ref "C47") (pin "1") (pinfunction "1_1") (pintype "passive"))
      (node (ref "C48") (pin "2") (pinfunction "2_2") (pintype "passive"))
      (node (ref "C49") (pin "2") (pinfunction "2_2") (pintype "passive"))
      (node (ref "C5") (pin "1") (pinfunction "1_1") (pintype "passive"))
      (node (ref "C50") (pin "1") (pinfunction "1_1") (pintype "passive"))
      (node (ref "C51") (pin "1") (pinfunction "1_1") (pintype "passive"))
      (node (ref "C6") (pin "2") (pinfunction "2_2") (pintype "passive"))
      (node (ref "C61") (pin "1") (pinfunction "1_1") (pintype "passive"))
      (node (ref "C62") (pin "1") (pinfunction "1_1") (pintype "passive"))
      (node (ref "C63") (pin "1") (pinfunction "1_1") (pintype "passive"))
      (node (ref "C67") (pin "1") (pinfunction "1_1") (pintype "passive"))
      (node (ref "C68") (pin "1") (pinfunction "1_1") (pintype "passive"))
      (node (ref "C69") (pin "1") (pinfunction "1_1") (pintype "passive"))
      (node (ref "C70") (pin "1") (pinfunction "1_1") (pintype "passive"))
      (node (ref "C71") (pin "1") (pinfunction "1_1") (pintype "passive"))
      (node (ref "C72") (pin "2") (pinfunction "2_2") (pintype "passive"))
      (node (ref "C73") (pin "1") (pinfunction "1_1") (pintype "passive"))
      (node (ref "C74") (pin "1") (pinfunction "1_1") (pintype "passive"))
      (node (ref "C75") (pin "1") (pinfunction "1_1") (pintype "passive"))
      (node (ref "C76") (pin "1") (pinfunction "1_1") (pintype "passive"))
      (node (ref "C77") (pin "1") (pinfunction "1_1") (pintype "passive"))
      (node (ref "C79") (pin "1") (pinfunction "1_1") (pintype "passive"))
      (node (ref "C8") (pin "-") (pinfunction "-_-") (pintype "passive"))
      (node (ref "C81") (pin "-") (pinfunction "-_-") (pintype "passive"))
      (node (ref "C82") (pin "1") (pinfunction "1_1") (pintype "passive"))
      (node (ref "C83") (pin "1") (pinfunction "1_1") (pintype "passive"))
      (node (ref "C84") (pin "2") (pinfunction "2_2") (pintype "passive"))
      (node (ref "C9") (pin "-") (pinfunction "-_-") (pintype "passive"))
      (node (ref "IC1") (pin "13") (pinfunction "GND_13") (pintype "power_in"))
      (node (ref "IC1") (pin "14") (pinfunction "GND_14") (pintype "power_in"))
      (node (ref "IC1") (pin "9") (pinfunction "COM_9") (pintype "input"))
      (node (ref "IC2") (pin "13") (pinfunction "GND_13") (pintype "power_in"))
      (node (ref "IC2") (pin "14") (pinfunction "GND_14") (pintype "power_in"))
      (node (ref "IC2") (pin "9") (pinfunction "COM_9") (pintype "input"))
      (node (ref "IC3") (pin "18") (pinfunction "GND_18") (pintype "power_in"))
      (node (ref "IC3") (pin "21") (pinfunction "GND_21") (pintype "power_in"))
      (node (ref "IC3") (pin "25") (pinfunction "GND_25") (pintype "power_in"))
      (node (ref "IC3") (pin "26") (pinfunction "TEST_26") (pintype "input"))
      (node (ref "IC3") (pin "7") (pinfunction "GND_7") (pintype "power_in"))
      (node (ref "JP1") (pin "GND") (pinfunction "GND_GND") (pintype "bidirectional"))
      (node (ref "LED1") (pin "C") (pinfunction "C_C") (pintype "passive"))
      (node (ref "R1") (pin "1") (pinfunction "1_1") (pintype "passive"))
      (node (ref "R12") (pin "1") (pinfunction "1_1") (pintype "passive"))
      (node (ref "R2") (pin "1") (pinfunction "1_1") (pintype "passive"))
      (node (ref "R3") (pin "2") (pinfunction "2_2") (pintype "passive"))
      (node (ref "R7") (pin "1") (pinfunction "1_1") (pintype "passive"))
      (node (ref "SV4") (pin "6") (pinfunction "6_6") (pintype "passive"))
      (node (ref "U$1") (pin "G10") (pinfunction "RES_10_G10") (pintype "bidirectional"))
      (node (ref "U$1") (pin "G11") (pinfunction "RES_11_G11") (pintype "bidirectional"))
      (node (ref "U$1") (pin "G12") (pinfunction "RES_12_G12") (pintype "bidirectional"))
      (node (ref "U$1") (pin "G13") (pinfunction "GND_G13") (pintype "bidirectional"))
      (node (ref "U$1") (pin "G4") (pinfunction "SDO/SA0_G4") (pintype "bidirectional"))
      (node (ref "U$1") (pin "G8") (pinfunction "RES_8_G8") (pintype "bidirectional"))
      (node (ref "U$1") (pin "G9") (pinfunction "RES_9_G9") (pintype "bidirectional"))
      (node (ref "U$2") (pin "G2") (pinfunction "ST_G2") (pintype "bidirectional"))
      (node (ref "U$2") (pin "G4") (pinfunction "GND_G4") (pintype "bidirectional"))
      (node (ref "U$2") (pin "G8") (pinfunction "SLEEP/PD_G8") (pintype "bidirectional"))
      (node (ref "U$3") (pin "P$2") (pinfunction "GND_P$2") (pintype "bidirectional"))
      (node (ref "U$4") (pin "G10") (pinfunction "RES_10_G10") (pintype "bidirectional"))
      (node (ref "U$4") (pin "G11") (pinfunction "RES_11_G11") (pintype "bidirectional"))
      (node (ref "U$4") (pin "G12") (pinfunction "RES_12_G12") (pintype "bidirectional"))
      (node (ref "U$4") (pin "G13") (pinfunction "GND_G13") (pintype "bidirectional"))
      (node (ref "U$4") (pin "G4") (pinfunction "SDO/SA0_G4") (pintype "bidirectional"))
      (node (ref "U$4") (pin "G8") (pinfunction "RES_8_G8") (pintype "bidirectional"))
      (node (ref "U$4") (pin "G9") (pinfunction "RES_9_G9") (pintype "bidirectional"))
      (node (ref "U$5") (pin "G2") (pinfunction "ST_G2") (pintype "bidirectional"))
      (node (ref "U$5") (pin "G4") (pinfunction "GND_G4") (pintype "bidirectional"))
      (node (ref "U$5") (pin "G8") (pinfunction "SLEEP/PD_G8") (pintype "bidirectional"))
      (node (ref "U1") (pin "18") (pinfunction "GND_2_18") (pintype "passive"))
      (node (ref "U1") (pin "19") (pinfunction "GND_19") (pintype "passive"))
      (node (ref "U10") (pin "2") (pinfunction "GND_2") (pintype "input"))
      (node (ref "U2") (pin "10") (pinfunction "RSVD_2_10") (pintype "passive"))
      (node (ref "U2") (pin "11") (pinfunction "AVSS_11") (pintype "passive"))
      (node (ref "U2") (pin "12") (pinfunction "RSVD_3_12") (pintype "passive"))
      (node (ref "U2") (pin "13") (pinfunction "DVSS_13") (pintype "passive"))
      (node (ref "U2") (pin "2") (pinfunction "RSVD_4_2") (pintype "passive"))
      (node (ref "U2") (pin "3") (pinfunction "RSVD_3") (pintype "passive"))
      (node (ref "U2") (pin "7") (pinfunction "PSS_7") (pintype "passive"))
      (node (ref "U3") (pin "F1") (pinfunction "AGND_2_F1") (pintype "passive"))
      (node (ref "U3") (pin "F4") (pinfunction "ST2_2_F4") (pintype "passive"))
      (node (ref "U3") (pin "F5") (pinfunction "ST1_2_F5") (pintype "passive"))
      (node (ref "U3") (pin "F7") (pinfunction "PGND_F7") (pintype "passive"))
      (node (ref "U3") (pin "G2") (pinfunction "AGND_G2") (pintype "passive"))
      (node (ref "U3") (pin "G4") (pinfunction "ST2_G4") (pintype "passive"))
      (node (ref "U3") (pin "G5") (pinfunction "ST1_G5") (pintype "passive"))
      (node (ref "U3") (pin "G6") (pinfunction "PGND_2_G6") (pintype "passive"))
      (node (ref "U4") (pin "F1") (pinfunction "AGND_F1") (pintype "passive"))
      (node (ref "U4") (pin "F4") (pinfunction "ST2_F4") (pintype "passive"))
      (node (ref "U4") (pin "F5") (pinfunction "ST1_F5") (pintype "passive"))
      (node (ref "U4") (pin "F7") (pinfunction "PGND_2_F7") (pintype "passive"))
      (node (ref "U4") (pin "G2") (pinfunction "AGND_2_G2") (pintype "passive"))
      (node (ref "U4") (pin "G4") (pinfunction "ST2_2_G4") (pintype "passive"))
      (node (ref "U4") (pin "G5") (pinfunction "ST1_2_G5") (pintype "passive"))
      (node (ref "U4") (pin "G6") (pinfunction "PGND_G6") (pintype "passive"))
      (node (ref "U5") (pin "10") (pinfunction "RSVDG_10") (pintype "bidirectional"))
      (node (ref "U5") (pin "11") (pinfunction "RSDVG_11") (pintype "bidirectional"))
      (node (ref "U5") (pin "12") (pinfunction "RSVDG_12") (pintype "bidirectional"))
      (node (ref "U5") (pin "13") (pinfunction "GND_13") (pintype "bidirectional"))
      (node (ref "U5") (pin "8") (pinfunction "RSVDG_8") (pintype "bidirectional"))
      (node (ref "U5") (pin "9") (pinfunction "RSVDG_9") (pintype "bidirectional"))
      (node (ref "U6") (pin "F1") (pinfunction "AGND_F1") (pintype "passive"))
      (node (ref "U6") (pin "F4") (pinfunction "ST2_F4") (pintype "passive"))
      (node (ref "U6") (pin "F5") (pinfunction "ST1_F5") (pintype "passive"))
      (node (ref "U6") (pin "F7") (pinfunction "PGND_2_F7") (pintype "passive"))
      (node (ref "U6") (pin "G2") (pinfunction "AGND_2_G2") (pintype "passive"))
      (node (ref "U6") (pin "G4") (pinfunction "ST2_2_G4") (pintype "passive"))
      (node (ref "U6") (pin "G5") (pinfunction "ST1_2_G5") (pintype "passive"))
      (node (ref "U6") (pin "G6") (pinfunction "PGND_G6") (pintype "passive"))
      (node (ref "U7") (pin "F1") (pinfunction "AGND_F1") (pintype "passive"))
      (node (ref "U7") (pin "F4") (pinfunction "ST2_F4") (pintype "passive"))
      (node (ref "U7") (pin "F5") (pinfunction "ST1_F5") (pintype "passive"))
      (node (ref "U7") (pin "F7") (pinfunction "PGND_2_F7") (pintype "passive"))
      (node (ref "U7") (pin "G2") (pinfunction "AGND_2_G2") (pintype "passive"))
      (node (ref "U7") (pin "G4") (pinfunction "ST2_2_G4") (pintype "passive"))
      (node (ref "U7") (pin "G5") (pinfunction "ST1_2_G5") (pintype "passive"))
      (node (ref "U7") (pin "G6") (pinfunction "PGND_G6") (pintype "passive"))
      (node (ref "U8") (pin "1") (pinfunction "CLKIN_1") (pintype "bidirectional"))
      (node (ref "U8") (pin "11") (pinfunction "FSYNC_11") (pintype "bidirectional"))
      (node (ref "U8") (pin "18") (pinfunction "GND_18") (pintype "bidirectional"))
      (node (ref "U9") (pin "21") (pinfunction "AGND_21") (pintype "bidirectional"))
      (node (ref "U9") (pin "3") (pinfunction "GND_3") (pintype "bidirectional"))
      (node (ref "U9") (pin "5") (pinfunction "GND_5") (pintype "bidirectional"))
    )
    (net (code "6") (name "MISO") (class "Default")
      (node (ref "IC1") (pin "15") (pinfunction "DOUT_15") (pintype "output"))
      (node (ref "IC2") (pin "15") (pinfunction "DOUT_15") (pintype "output"))
      (node (ref "SV4") (pin "1") (pinfunction "1_1") (pintype "passive"))
      (node (ref "U1") (pin "2") (pinfunction "DOUT_2") (pintype "passive"))
      (node (ref "U2") (pin "5") (pinfunction "MISO_5") (pintype "passive"))
      (node (ref "U9") (pin "16") (pinfunction "PB4(MISO)_16") (pintype "bidirectional"))
    )
    (net (code "7") (name "MOSI") (class "Default")
      (node (ref "IC1") (pin "17") (pinfunction "DI_17") (pintype "input"))
      (node (ref "IC2") (pin "17") (pinfunction "DI_17") (pintype "input"))
      (node (ref "SV4") (pin "4") (pinfunction "4_4") (pintype "passive"))
      (node (ref "U1") (pin "3") (pinfunction "DIN_3") (pintype "passive"))
      (node (ref "U2") (pin "15") (pinfunction "MOSI_15") (pintype "passive"))
      (node (ref "U9") (pin "15") (pinfunction "PB3(MOSI/OC2)_15") (pintype "bidirectional"))
    )
    (net (code "8") (name "N$45") (class "Default")
      (node (ref "SV1") (pin "7") (pinfunction "7_7") (pintype "passive"))
      (node (ref "U9") (pin "19") (pinfunction "ADC6_19") (pintype "bidirectional"))
    )
    (net (code "9") (name "N$54") (class "Default")
      (node (ref "SV1") (pin "8") (pinfunction "8_8") (pintype "passive"))
      (node (ref "U9") (pin "22") (pinfunction "ADC7_22") (pintype "bidirectional"))
    )
    (net (code "10") (name "N$81") (class "Default")
      (node (ref "U9") (pin "12") (pinfunction "PB0(ICP)_12") (pintype "bidirectional"))
    )
    (net (code "11") (name "N$82") (class "Default")
      (node (ref "U9") (pin "13") (pinfunction "PB1(OC1A)_13") (pintype "bidirectional"))
    )
    (net (code "12") (name "N$83") (class "Default")
      (node (ref "U9") (pin "14") (pinfunction "PB2(SS/OC1B)_14") (pintype "bidirectional"))
    )
    (net (code "13") (name "Net-(C7-Pad2)") (class "Default")
      (node (ref "C7") (pin "2") (pinfunction "2_2") (pintype "passive"))
      (node (ref "R1") (pin "2") (pinfunction "2_2") (pintype "passive"))
    )
    (net (code "14") (name "Net-(C11-Pad1)") (class "Default")
      (node (ref "C11") (pin "1") (pinfunction "1_1") (pintype "passive"))
      (node (ref "R2") (pin "2") (pinfunction "2_2") (pintype "passive"))
    )
    (net (code "15") (name "Net-(C21-Pad2)") (class "Default")
      (node (ref "C21") (pin "2") (pinfunction "2_2") (pintype "passive"))
      (node (ref "R3") (pin "1") (pinfunction "1_1") (pintype "passive"))
    )
    (net (code "16") (name "Net-(C26-Pad2)") (class "Default")
      (node (ref "C26") (pin "2") (pinfunction "2_2") (pintype "passive"))
      (node (ref "R12") (pin "2") (pinfunction "2_2") (pintype "passive"))
    )
    (net (code "17") (name "Net-(C83-Pad2)") (class "Default")
      (node (ref "C83") (pin "2") (pinfunction "2_2") (pintype "passive"))
      (node (ref "JP1") (pin "VBUS") (pinfunction "VBUS_VBUS") (pintype "bidirectional"))
      (node (ref "L2") (pin "1") (pinfunction "1_1") (pintype "passive"))
    )
    (net (code "18") (name "Net-(IC1-CH0)") (class "Default")
      (node (ref "C37") (pin "2") (pinfunction "2_2") (pintype "passive"))
      (node (ref "IC1") (pin "1") (pinfunction "CH0_1") (pintype "input"))
      (node (ref "R13") (pin "1") (pinfunction "1_1") (pintype "passive"))
    )
    (net (code "19") (name "Net-(IC1-CH1)") (class "Default")
      (node (ref "C41") (pin "2") (pinfunction "2_2") (pintype "passive"))
      (node (ref "IC1") (pin "2") (pinfunction "CH1_2") (pintype "input"))
      (node (ref "R14") (pin "1") (pinfunction "1_1") (pintype "passive"))
    )
    (net (code "20") (name "Net-(IC1-CH2)") (class "Default")
      (node (ref "C42") (pin "2") (pinfunction "2_2") (pintype "passive"))
      (node (ref "IC1") (pin "3") (pinfunction "CH2_3") (pintype "input"))
      (node (ref "R15") (pin "1") (pinfunction "1_1") (pintype "passive"))
    )
    (net (code "21") (name "Net-(IC1-CH3)") (class "Default")
      (node (ref "C47") (pin "2") (pinfunction "2_2") (pintype "passive"))
      (node (ref "IC1") (pin "4") (pinfunction "CH3_4") (pintype "input"))
      (node (ref "R20") (pin "1") (pinfunction "1_1") (pintype "passive"))
    )
    (net (code "22") (name "Net-(IC1-CH4)") (class "Default")
      (node (ref "C46") (pin "1") (pinfunction "1_1") (pintype "passive"))
      (node (ref "IC1") (pin "5") (pinfunction "CH4_5") (pintype "input"))
      (node (ref "R19") (pin "2") (pinfunction "2_2") (pintype "passive"))
    )
    (net (code "23") (name "Net-(IC1-CH5)") (class "Default")
      (node (ref "C45") (pin "1") (pinfunction "1_1") (pintype "passive"))
      (node (ref "IC1") (pin "6") (pinfunction "CH5_6") (pintype "input"))
      (node (ref "R18") (pin "2") (pinfunction "2_2") (pintype "passive"))
    )
    (net (code "24") (name "Net-(IC1-CH6)") (class "Default")
      (node (ref "C44") (pin "1") (pinfunction "1_1") (pintype "passive"))
      (node (ref "IC1") (pin "7") (pinfunction "CH6_7") (pintype "input"))
      (node (ref "R17") (pin "2") (pinfunction "2_2") (pintype "passive"))
    )
    (net (code "25") (name "Net-(IC1-CH7)") (class "Default")
      (node (ref "C43") (pin "1") (pinfunction "1_1") (pintype "passive"))
      (node (ref "IC1") (pin "8") (pinfunction "CH7_8") (pintype "input"))
      (node (ref "R16") (pin "2") (pinfunction "2_2") (pintype "passive"))
    )
    (net (code "26") (name "Net-(IC2-CH0)") (class "Default")
      (node (ref "C50") (pin "2") (pinfunction "2_2") (pintype "passive"))
      (node (ref "IC2") (pin "1") (pinfunction "CH0_1") (pintype "input"))
      (node (ref "R21") (pin "1") (pinfunction "1_1") (pintype "passive"))
    )
    (net (code "27") (name "Net-(IC2-CH1)") (class "Default")
      (node (ref "C51") (pin "2") (pinfunction "2_2") (pintype "passive"))
      (node (ref "IC2") (pin "2") (pinfunction "CH1_2") (pintype "input"))
      (node (ref "R22") (pin "1") (pinfunction "1_1") (pintype "passive"))
    )
    (net (code "28") (name "Net-(IC3-CBUS0)") (class "Default")
      (node (ref "IC3") (pin "23") (pinfunction "CBUS0_23") (pintype "bidirectional"))
      (node (ref "LED2") (pin "C") (pinfunction "C_C") (pintype "passive"))
    )
    (net (code "29") (name "Net-(IC3-CBUS1)") (class "Default")
      (node (ref "IC3") (pin "22") (pinfunction "CBUS1_22") (pintype "bidirectional"))
      (node (ref "LED3") (pin "C") (pinfunction "C_C") (pintype "passive"))
    )
    (net (code "30") (name "Net-(IC3-RXD)") (class "Default")
      (node (ref "IC3") (pin "5") (pinfunction "RXD_5") (pintype "input"))
      (node (ref "R11") (pin "2") (pinfunction "2_2") (pintype "passive"))
    )
    (net (code "31") (name "Net-(IC3-TXD)") (class "Default")
      (node (ref "IC3") (pin "1") (pinfunction "TXD_1") (pintype "output"))
      (node (ref "R10") (pin "2") (pinfunction "2_2") (pintype "passive"))
    )
    (net (code "32") (name "Net-(IC3-USBDM)") (class "Default")
      (node (ref "IC3") (pin "16") (pinfunction "USBDM_16") (pintype "bidirectional"))
      (node (ref "JP1") (pin "D-") (pinfunction "D-_D-") (pintype "bidirectional"))
    )
    (net (code "33") (name "Net-(IC3-USBDP)") (class "Default")
      (node (ref "IC3") (pin "15") (pinfunction "USBDP_15") (pintype "bidirectional"))
      (node (ref "JP1") (pin "D+") (pinfunction "D+_D+") (pintype "bidirectional"))
    )
    (net (code "34") (name "Net-(IC3-~{CTS})") (class "Default")
      (node (ref "IC3") (pin "11") (pinfunction "~{CTS}_11") (pintype "input"))
      (node (ref "SV5") (pin "1") (pinfunction "1_1") (pintype "passive"))
    )
    (net (code "35") (name "Net-(IC3-~{DCD})") (class "Default")
      (node (ref "IC3") (pin "10") (pinfunction "~{DCD}_10") (pintype "input"))
      (node (ref "SV5") (pin "3") (pinfunction "3_3") (pintype "passive"))
    )
    (net (code "36") (name "Net-(IC3-~{DSR})") (class "Default")
      (node (ref "IC3") (pin "9") (pinfunction "~{DSR}_9") (pintype "input"))
      (node (ref "SV5") (pin "2") (pinfunction "2_2") (pintype "passive"))
    )
    (net (code "37") (name "Net-(IC3-~{DTR})") (class "Default")
      (node (ref "C78") (pin "1") (pinfunction "1_1") (pintype "passive"))
      (node (ref "IC3") (pin "2") (pinfunction "~{DTR}_2") (pintype "output"))
    )
    (net (code "38") (name "Net-(IC3-~{RI})") (class "Default")
      (node (ref "IC3") (pin "6") (pinfunction "~{RI}_6") (pintype "input"))
      (node (ref "SV5") (pin "4") (pinfunction "4_4") (pintype "passive"))
    )
    (net (code "39") (name "Net-(LED1-PadA)") (class "Default")
      (node (ref "LED1") (pin "A") (pinfunction "A_A") (pintype "passive"))
      (node (ref "R4") (pin "1") (pinfunction "1_1") (pintype "passive"))
    )
    (net (code "40") (name "Net-(LED2-PadA)") (class "Default")
      (node (ref "LED2") (pin "A") (pinfunction "A_A") (pintype "passive"))
      (node (ref "R29") (pin "2") (pinfunction "2_2") (pintype "passive"))
    )
    (net (code "41") (name "Net-(LED3-PadA)") (class "Default")
      (node (ref "LED3") (pin "A") (pinfunction "A_A") (pintype "passive"))
      (node (ref "R30") (pin "2") (pinfunction "2_2") (pintype "passive"))
    )
    (net (code "42") (name "Net-(U$1-PLLFILT)") (class "Default")
      (node (ref "C10") (pin "2") (pinfunction "2_2") (pintype "passive"))
      (node (ref "C11") (pin "2") (pinfunction "2_2") (pintype "passive"))
      (node (ref "U$1") (pin "G14") (pinfunction "PLLFILT_G14") (pintype "bidirectional"))
    )
    (net (code "43") (name "Net-(U$2-VCONT)") (class "Default")
      (node (ref "C6") (pin "1") (pinfunction "1_1") (pintype "passive"))
      (node (ref "C7") (pin "1") (pinfunction "1_1") (pintype "passive"))
      (node (ref "U$2") (pin "G3") (pinfunction "VCONT_G3") (pintype "bidirectional"))
    )
    (net (code "44") (name "Net-(U$3-FB)") (class "Default")
      (node (ref "C22") (pin "2") (pinfunction "2_2") (pintype "passive"))
      (node (ref "R7") (pin "2") (pinfunction "2_2") (pintype "passive"))
      (node (ref "R8") (pin "1") (pinfunction "1_1") (pintype "passive"))
      (node (ref "U$3") (pin "P$3") (pinfunction "FB_P$3") (pintype "bidirectional"))
    )
    (net (code "45") (name "Net-(U$3-SW)") (class "Default")
      (node (ref "D1") (pin "A") (pinfunction "A_A") (pintype "passive"))
      (node (ref "L1") (pin "2") (pinfunction "2_2") (pintype "passive"))
      (node (ref "U$3") (pin "P$1") (pinfunction "SW_P$1") (pintype "bidirectional"))
    )
    (net (code "46") (name "Net-(U$4-PLLFILT)") (class "Default")
      (node (ref "C23") (pin "2") (pinfunction "2_2") (pintype "passive"))
      (node (ref "U$4") (pin "G14") (pinfunction "PLLFILT_G14") (pintype "bidirectional"))
    )
    (net (code "47") (name "Net-(U$5-VCONT)") (class "Default")
      (node (ref "C25") (pin "1") (pinfunction "1_1") (pintype "passive"))
      (node (ref "C26") (pin "1") (pinfunction "1_1") (pintype "passive"))
      (node (ref "U$5") (pin "G3") (pinfunction "VCONT_G3") (pintype "bidirectional"))
    )
    (net (code "48") (name "Net-(U2-AVDD)") (class "Default")
      (node (ref "C1") (pin "2") (pinfunction "2_2") (pintype "passive"))
      (node (ref "U2") (pin "14") (pinfunction "AVDD_14") (pintype "passive"))
    )
    (net (code "49") (name "Net-(U2-CPS)") (class "Default")
      (node (ref "C4") (pin "2") (pinfunction "2_2") (pintype "passive"))
      (node (ref "D2") (pin "C") (pinfunction "C_C") (pintype "passive"))
      (node (ref "U2") (pin "9") (pinfunction "CPS_9") (pintype "passive"))
    )
    (net (code "50") (name "Net-(U2-DVDD)") (class "Default")
      (node (ref "C2") (pin "2") (pinfunction "2_2") (pintype "passive"))
      (node (ref "U2") (pin "1") (pinfunction "DVDD_1") (pintype "passive"))
    )
    (net (code "51") (name "Net-(U2-VX)") (class "Default")
      (node (ref "D2") (pin "A") (pinfunction "A_A") (pintype "passive"))
      (node (ref "L3") (pin "2") (pinfunction "2_2") (pintype "passive"))
      (node (ref "U2") (pin "8") (pinfunction "VX_8") (pintype "passive"))
    )
    (net (code "52") (name "Net-(U3-CP1)") (class "Default")
      (node (ref "C12") (pin "2") (pinfunction "2_2") (pintype "passive"))
      (node (ref "U3") (pin "A5") (pinfunction "CP1_2_A5") (pintype "passive"))
      (node (ref "U3") (pin "B5") (pinfunction "CP1_B5") (pintype "passive"))
    )
    (net (code "53") (name "Net-(U3-CP2)") (class "Default")
      (node (ref "C12") (pin "1") (pinfunction "1_1") (pintype "passive"))
      (node (ref "U3") (pin "A4") (pinfunction "CP2_2_A4") (pintype "passive"))
      (node (ref "U3") (pin "B4") (pinfunction "CP2_B4") (pintype "passive"))
    )
    (net (code "54") (name "Net-(U3-CP3)") (class "Default")
      (node (ref "C13") (pin "1") (pinfunction "1_1") (pintype "passive"))
      (node (ref "U3") (pin "C6") (pinfunction "CP3_2_C6") (pintype "passive"))
      (node (ref "U3") (pin "C7") (pinfunction "CP3_C7") (pintype "passive"))
    )
    (net (code "55") (name "Net-(U3-CP4)") (class "Default")
      (node (ref "C13") (pin "2") (pinfunction "2_2") (pintype "passive"))
      (node (ref "U3") (pin "A6") (pinfunction "CP4_2_A6") (pintype "passive"))
      (node (ref "U3") (pin "B7") (pinfunction "CP4_B7") (pintype "passive"))
    )
    (net (code "56") (name "Net-(U3-CP5)") (class "Default")
      (node (ref "C16") (pin "2") (pinfunction "2_2") (pintype "passive"))
      (node (ref "U3") (pin "D6") (pinfunction "CP5_2_D6") (pintype "passive"))
      (node (ref "U3") (pin "D7") (pinfunction "CP5_D7") (pintype "passive"))
    )
    (net (code "57") (name "Net-(U3-SUMJ)") (class "Default")
      (node (ref "C14") (pin "1") (pinfunction "1_1") (pintype "passive"))
      (node (ref "U3") (pin "C1") (pinfunction "SUMJ_C1") (pintype "passive"))
      (node (ref "U3") (pin "C2") (pinfunction "SUMJ_2_C2") (pintype "passive"))
    )
    (net (code "58") (name "Net-(U4-CP1)") (class "Default")
      (node (ref "C27") (pin "2") (pinfunction "2_2") (pintype "passive"))
      (node (ref "U4") (pin "A5") (pinfunction "CP1_A5") (pintype "passive"))
      (node (ref "U4") (pin "B5") (pinfunction "CP1_2_B5") (pintype "passive"))
    )
    (net (code "59") (name "Net-(U4-CP2)") (class "Default")
      (node (ref "C27") (pin "1") (pinfunction "1_1") (pintype "passive"))
      (node (ref "U4") (pin "A4") (pinfunction "CP2_A4") (pintype "passive"))
      (node (ref "U4") (pin "B4") (pinfunction "CP2_2_B4") (pintype "passive"))
    )
    (net (code "60") (name "Net-(U4-CP3)") (class "Default")
      (node (ref "C28") (pin "1") (pinfunction "1_1") (pintype "passive"))
      (node (ref "U4") (pin "C6") (pinfunction "CP3_C6") (pintype "passive"))
      (node (ref "U4") (pin "C7") (pinfunction "CP3_2_C7") (pintype "passive"))
    )
    (net (code "61") (name "Net-(U4-CP4)") (class "Default")
      (node (ref "C28") (pin "2") (pinfunction "2_2") (pintype "passive"))
      (node (ref "U4") (pin "A6") (pinfunction "CP4_A6") (pintype "passive"))
      (node (ref "U4") (pin "B7") (pinfunction "CP4_2_B7") (pintype "passive"))
    )
    (net (code "62") (name "Net-(U4-CP5)") (class "Default")
      (node (ref "C30") (pin "2") (pinfunction "2_2") (pintype "passive"))
      (node (ref "U4") (pin "D6") (pinfunction "CP5_D6") (pintype "passive"))
      (node (ref "U4") (pin "D7") (pinfunction "CP5_2_D7") (pintype "passive"))
    )
    (net (code "63") (name "Net-(U4-SUMJ)") (class "Default")
      (node (ref "C29") (pin "1") (pinfunction "1_1") (pintype "passive"))
      (node (ref "U4") (pin "C1") (pinfunction "SUMJ_C1") (pintype "passive"))
      (node (ref "U4") (pin "C2") (pinfunction "SUMJ_2_C2") (pintype "passive"))
    )
    (net (code "64") (name "Net-(U5-PLL)") (class "Default")
      (node (ref "C21") (pin "1") (pinfunction "1_1") (pintype "passive"))
      (node (ref "C72") (pin "1") (pinfunction "1_1") (pintype "passive"))
      (node (ref "U5") (pin "14") (pinfunction "PLL_14") (pintype "bidirectional"))
    )
    (net (code "65") (name "Net-(U6-CP1)") (class "Default")
      (node (ref "C58") (pin "2") (pinfunction "2_2") (pintype "passive"))
      (node (ref "U6") (pin "A5") (pinfunction "CP1_A5") (pintype "passive"))
      (node (ref "U6") (pin "B5") (pinfunction "CP1_2_B5") (pintype "passive"))
    )
    (net (code "66") (name "Net-(U6-CP2)") (class "Default")
      (node (ref "C58") (pin "1") (pinfunction "1_1") (pintype "passive"))
      (node (ref "U6") (pin "A4") (pinfunction "CP2_A4") (pintype "passive"))
      (node (ref "U6") (pin "B4") (pinfunction "CP2_2_B4") (pintype "passive"))
    )
    (net (code "67") (name "Net-(U6-CP3)") (class "Default")
      (node (ref "C59") (pin "1") (pinfunction "1_1") (pintype "passive"))
      (node (ref "U6") (pin "C6") (pinfunction "CP3_C6") (pintype "passive"))
      (node (ref "U6") (pin "C7") (pinfunction "CP3_2_C7") (pintype "passive"))
    )
    (net (code "68") (name "Net-(U6-CP4)") (class "Default")
      (node (ref "C59") (pin "2") (pinfunction "2_2") (pintype "passive"))
      (node (ref "U6") (pin "A6") (pinfunction "CP4_A6") (pintype "passive"))
      (node (ref "U6") (pin "B7") (pinfunction "CP4_2_B7") (pintype "passive"))
    )
    (net (code "69") (name "Net-(U6-CP5)") (class "Default")
      (node (ref "C61") (pin "2") (pinfunction "2_2") (pintype "passive"))
      (node (ref "U6") (pin "D6") (pinfunction "CP5_D6") (pintype "passive"))
      (node (ref "U6") (pin "D7") (pinfunction "CP5_2_D7") (pintype "passive"))
    )
    (net (code "70") (name "Net-(U6-SUMJ)") (class "Default")
      (node (ref "C60") (pin "1") (pinfunction "1_1") (pintype "passive"))
      (node (ref "U6") (pin "C1") (pinfunction "SUMJ_C1") (pintype "passive"))
      (node (ref "U6") (pin "C2") (pinfunction "SUMJ_2_C2") (pintype "passive"))
    )
    (net (code "71") (name "Net-(U7-CP1)") (class "Default")
      (node (ref "C64") (pin "2") (pinfunction "2_2") (pintype "passive"))
      (node (ref "U7") (pin "A5") (pinfunction "CP1_A5") (pintype "passive"))
      (node (ref "U7") (pin "B5") (pinfunction "CP1_2_B5") (pintype "passive"))
    )
    (net (code "72") (name "Net-(U7-CP2)") (class "Default")
      (node (ref "C64") (pin "1") (pinfunction "1_1") (pintype "passive"))
      (node (ref "U7") (pin "A4") (pinfunction "CP2_A4") (pintype "passive"))
      (node (ref "U7") (pin "B4") (pinfunction "CP2_2_B4") (pintype "passive"))
    )
    (net (code "73") (name "Net-(U7-CP3)") (class "Default")
      (node (ref "C65") (pin "1") (pinfunction "1_1") (pintype "passive"))
      (node (ref "U7") (pin "C6") (pinfunction "CP3_C6") (pintype "passive"))
      (node (ref "U7") (pin "C7") (pinfunction "CP3_2_C7") (pintype "passive"))
    )
    (net (code "74") (name "Net-(U7-CP4)") (class "Default")
      (node (ref "C65") (pin "2") (pinfunction "2_2") (pintype "passive"))
      (node (ref "U7") (pin "A6") (pinfunction "CP4_A6") (pintype "passive"))
      (node (ref "U7") (pin "B7") (pinfunction "CP4_2_B7") (pintype "passive"))
    )
    (net (code "75") (name "Net-(U7-CP5)") (class "Default")
      (node (ref "C67") (pin "2") (pinfunction "2_2") (pintype "passive"))
      (node (ref "U7") (pin "D6") (pinfunction "CP5_D6") (pintype "passive"))
      (node (ref "U7") (pin "D7") (pinfunction "CP5_2_D7") (pintype "passive"))
    )
    (net (code "76") (name "Net-(U7-SUMJ)") (class "Default")
      (node (ref "C66") (pin "1") (pinfunction "1_1") (pintype "passive"))
      (node (ref "U7") (pin "C1") (pinfunction "SUMJ_C1") (pintype "passive"))
      (node (ref "U7") (pin "C2") (pinfunction "SUMJ_2_C2") (pintype "passive"))
    )
    (net (code "77") (name "Net-(U8-CPOUT)") (class "Default")
      (node (ref "C71") (pin "2") (pinfunction "2_2") (pintype "passive"))
      (node (ref "U8") (pin "20") (pinfunction "CPOUT_20") (pintype "bidirectional"))
    )
    (net (code "78") (name "Net-(U8-REGOUT)") (class "Default")
      (node (ref "C70") (pin "2") (pinfunction "2_2") (pintype "passive"))
      (node (ref "U8") (pin "10") (pinfunction "REGOUT_10") (pintype "bidirectional"))
    )
    (net (code "79") (name "Net-(U8-VLOGIC)") (class "Default")
      (node (ref "C73") (pin "2") (pinfunction "2_2") (pintype "passive"))
      (node (ref "U8") (pin "8") (pinfunction "VLOGIC_8") (pintype "bidirectional"))
    )
    (net (code "80") (name "Net-(U9-PB6(XTAL1{slash}TOSC1))") (class "Default")
      (node (ref "C24") (pin "2") (pinfunction "2_2") (pintype "passive"))
      (node (ref "U9") (pin "7") (pinfunction "PB6(XTAL1/TOSC1)_7") (pintype "bidirectional"))
      (node (ref "Y1") (pin "2") (pinfunction "2_2") (pintype "passive"))
    )
    (net (code "81") (name "Net-(U9-PB7(XTAL2{slash}TOSC2))") (class "Default")
      (node (ref "C74") (pin "2") (pinfunction "2_2") (pintype "passive"))
      (node (ref "U9") (pin "8") (pinfunction "PB7(XTAL2/TOSC2)_8") (pintype "bidirectional"))
      (node (ref "Y1") (pin "1") (pinfunction "1_1") (pintype "passive"))
    )
    (net (code "82") (name "OUTZ_ADXRS622") (class "Default")
      (node (ref "C66") (pin "2") (pinfunction "2_2") (pintype "passive"))
      (node (ref "R15") (pin "2") (pinfunction "2_2") (pintype "passive"))
      (node (ref "U7") (pin "A2") (pinfunction "RATEOUT_2_A2") (pintype "passive"))
      (node (ref "U7") (pin "B1") (pinfunction "RATEOUT_B1") (pintype "passive"))
    )
    (net (code "83") (name "OUTZ_ADXRS642") (class "Default")
      (node (ref "C60") (pin "2") (pinfunction "2_2") (pintype "passive"))
      (node (ref "R19") (pin "1") (pinfunction "1_1") (pintype "passive"))
      (node (ref "U6") (pin "A2") (pinfunction "RATEOUT_2_A2") (pintype "passive"))
      (node (ref "U6") (pin "B1") (pinfunction "RATEOUT_B1") (pintype "passive"))
    )
    (net (code "84") (name "OUTZ_ADXRS646") (class "Default")
      (node (ref "C14") (pin "2") (pinfunction "2_2") (pintype "passive"))
      (node (ref "R13") (pin "2") (pinfunction "2_2") (pintype "passive"))
      (node (ref "U3") (pin "A2") (pinfunction "RATEOUT_2_A2") (pintype "passive"))
      (node (ref "U3") (pin "B1") (pinfunction "RATEOUT_B1") (pintype "passive"))
    )
    (net (code "85") (name "OUTZ_ADXRS652") (class "Default")
      (node (ref "C29") (pin "2") (pinfunction "2_2") (pintype "passive"))
      (node (ref "R17") (pin "1") (pinfunction "1_1") (pintype "passive"))
      (node (ref "U4") (pin "A2") (pinfunction "RATEOUT_2_A2") (pintype "passive"))
      (node (ref "U4") (pin "B1") (pinfunction "RATEOUT_B1") (pintype "passive"))
    )
    (net (code "86") (name "OUTZ_LY330") (class "Default")
      (node (ref "R21") (pin "2") (pinfunction "2_2") (pintype "passive"))
      (node (ref "U$2") (pin "G6") (pinfunction "OUTZ_G6") (pintype "bidirectional"))
    )
    (net (code "87") (name "OUTZ_LY3200") (class "Default")
      (node (ref "R22") (pin "2") (pinfunction "2_2") (pintype "passive"))
      (node (ref "U$5") (pin "G6") (pinfunction "OUTZ_G6") (pintype "bidirectional"))
    )
    (net (code "88") (name "RESET") (class "Default")
      (node (ref "C78") (pin "2") (pinfunction "2_2") (pintype "passive"))
      (node (ref "IC3") (pin "3") (pinfunction "~{RTS}_3") (pintype "output"))
      (node (ref "R9") (pin "1") (pinfunction "1_1") (pintype "passive"))
      (node (ref "SV4") (pin "5") (pinfunction "5_5") (pintype "passive"))
      (node (ref "U9") (pin "29") (pinfunction "PC6(/RESET)_29") (pintype "bidirectional"))
    )
    (net (code "89") (name "RXD") (class "Default")
      (node (ref "R10") (pin "1") (pinfunction "1_1") (pintype "passive"))
      (node (ref "U9") (pin "30") (pinfunction "PD0(RXD)_30") (pintype "bidirectional"))
    )
    (net (code "90") (name "SCLK") (class "Default")
      (node (ref "IC1") (pin "19") (pinfunction "DCLK_19") (pintype "input"))
      (node (ref "IC2") (pin "19") (pinfunction "DCLK_19") (pintype "input"))
      (node (ref "SV4") (pin "3") (pinfunction "3_3") (pintype "passive"))
      (node (ref "U1") (pin "1") (pinfunction "SCLK_1") (pintype "passive"))
      (node (ref "U2") (pin "16") (pinfunction "SCLK_16") (pintype "passive"))
      (node (ref "U9") (pin "17") (pinfunction "PB5(SCK)_17") (pintype "bidirectional"))
    )
    (net (code "91") (name "SCL_3.3V") (class "Default")
      (node (ref "Q2") (pin "2") (pinfunction "S_2") (pintype "passive"))
      (node (ref "R31") (pin "1") (pinfunction "1_1") (pintype "passive"))
      (node (ref "U$1") (pin "G2") (pinfunction "SPC/SCL_G2") (pintype "bidirectional"))
      (node (ref "U$4") (pin "G2") (pinfunction "SPC/SCL_G2") (pintype "bidirectional"))
      (node (ref "U5") (pin "2") (pinfunction "SCL_2") (pintype "bidirectional"))
      (node (ref "U8") (pin "23") (pinfunction "SCL_23") (pintype "bidirectional"))
    )
    (net (code "92") (name "SCL_5V") (class "Default")
      (node (ref "Q2") (pin "3") (pinfunction "D_3") (pintype "passive"))
      (node (ref "R32") (pin "1") (pinfunction "1_1") (pintype "passive"))
      (node (ref "SV1") (pin "6") (pinfunction "6_6") (pintype "passive"))
      (node (ref "U9") (pin "28") (pinfunction "PC5(ADC5/SCL)_28") (pintype "bidirectional"))
    )
    (net (code "93") (name "SDA_3.3V") (class "Default")
      (node (ref "Q1") (pin "2") (pinfunction "S_2") (pintype "passive"))
      (node (ref "R5") (pin "1") (pinfunction "1_1") (pintype "passive"))
      (node (ref "U$1") (pin "G3") (pinfunction "SDA/SDI/SDO_G3") (pintype "bidirectional"))
      (node (ref "U$4") (pin "G3") (pinfunction "SDA/SDI/SDO_G3") (pintype "bidirectional"))
      (node (ref "U5") (pin "3") (pinfunction "SDA/SDI_3") (pintype "bidirectional"))
      (node (ref "U8") (pin "24") (pinfunction "SDA_24") (pintype "bidirectional"))
    )
    (net (code "94") (name "SDA_5V") (class "Default")
      (node (ref "Q1") (pin "3") (pinfunction "D_3") (pintype "passive"))
      (node (ref "R6") (pin "1") (pinfunction "1_1") (pintype "passive"))
      (node (ref "SV1") (pin "5") (pinfunction "5_5") (pintype "passive"))
      (node (ref "U9") (pin "27") (pinfunction "PC4(ADC4/SDA)_27") (pintype "bidirectional"))
    )
    (net (code "95") (name "TEMP_ADXRS622") (class "Default")
      (node (ref "R20") (pin "2") (pinfunction "2_2") (pintype "passive"))
      (node (ref "U7") (pin "F3") (pinfunction "TEMP_F3") (pintype "passive"))
      (node (ref "U7") (pin "G3") (pinfunction "TEMP_2_G3") (pintype "passive"))
    )
    (net (code "96") (name "TEMP_ADXRS642") (class "Default")
      (node (ref "R18") (pin "1") (pinfunction "1_1") (pintype "passive"))
      (node (ref "U6") (pin "F3") (pinfunction "TEMP_F3") (pintype "passive"))
      (node (ref "U6") (pin "G3") (pinfunction "TEMP_2_G3") (pintype "passive"))
    )
    (net (code "97") (name "TEMP_ADXRS646") (class "Default")
      (node (ref "R14") (pin "2") (pinfunction "2_2") (pintype "passive"))
      (node (ref "U3") (pin "F3") (pinfunction "TEMP_2_F3") (pintype "passive"))
      (node (ref "U3") (pin "G3") (pinfunction "TEMP_G3") (pintype "passive"))
    )
    (net (code "98") (name "TEMP_ADXRS652") (class "Default")
      (node (ref "R16") (pin "1") (pinfunction "1_1") (pintype "passive"))
      (node (ref "U4") (pin "F3") (pinfunction "TEMP_F3") (pintype "passive"))
      (node (ref "U4") (pin "G3") (pinfunction "TEMP_2_G3") (pintype "passive"))
    )
    (net (code "99") (name "TXD") (class "Default")
      (node (ref "R11") (pin "1") (pinfunction "1_1") (pintype "passive"))
      (node (ref "U9") (pin "31") (pinfunction "PD1(TXD)_31") (pintype "bidirectional"))
    )
    (net (code "100") (name "unconnected-(IC1-BUSY-Pad16)") (class "Default")
      (node (ref "IC1") (pin "16") (pinfunction "BUSY_16") (pintype "output"))
    )
    (net (code "101") (name "unconnected-(IC2-BUSY-Pad16)") (class "Default")
      (node (ref "IC2") (pin "16") (pinfunction "BUSY_16") (pintype "output"))
    )
    (net (code "102") (name "unconnected-(IC2-CH2-Pad3)") (class "Default")
      (node (ref "IC2") (pin "3") (pinfunction "CH2_3") (pintype "input"))
    )
    (net (code "103") (name "unconnected-(IC2-CH3-Pad4)") (class "Default")
      (node (ref "IC2") (pin "4") (pinfunction "CH3_4") (pintype "input"))
    )
    (net (code "104") (name "unconnected-(IC2-CH4-Pad5)") (class "Default")
      (node (ref "IC2") (pin "5") (pinfunction "CH4_5") (pintype "input"))
    )
    (net (code "105") (name "unconnected-(IC2-CH5-Pad6)") (class "Default")
      (node (ref "IC2") (pin "6") (pinfunction "CH5_6") (pintype "input"))
    )
    (net (code "106") (name "unconnected-(IC2-CH6-Pad7)") (class "Default")
      (node (ref "IC2") (pin "7") (pinfunction "CH6_7") (pintype "input"))
    )
    (net (code "107") (name "unconnected-(IC2-CH7-Pad8)") (class "Default")
      (node (ref "IC2") (pin "8") (pinfunction "CH7_8") (pintype "input"))
    )
    (net (code "108") (name "unconnected-(IC3-3V3OUT-Pad17)") (class "Default")
      (node (ref "IC3") (pin "17") (pinfunction "3V3OUT_17") (pintype "output"))
    )
    (net (code "109") (name "unconnected-(IC3-CBUS2-Pad13)") (class "Default")
      (node (ref "IC3") (pin "13") (pinfunction "CBUS2_13") (pintype "bidirectional"))
    )
    (net (code "110") (name "unconnected-(IC3-CBUS3-Pad14)") (class "Default")
      (node (ref "IC3") (pin "14") (pinfunction "CBUS3_14") (pintype "bidirectional"))
    )
    (net (code "111") (name "unconnected-(IC3-CBUS4-Pad12)") (class "Default")
      (node (ref "IC3") (pin "12") (pinfunction "CBUS4_12") (pintype "bidirectional"))
    )
    (net (code "112") (name "unconnected-(IC3-OSCI-Pad27)") (class "Default")
      (node (ref "IC3") (pin "27") (pinfunction "OSCI_27") (pintype "input"))
    )
    (net (code "113") (name "unconnected-(IC3-OSCO-Pad28)") (class "Default")
      (node (ref "IC3") (pin "28") (pinfunction "OSCO_28") (pintype "output"))
    )
    (net (code "114") (name "unconnected-(U$1-DRDY{slash}INT2-PadG6)") (class "Default")
      (node (ref "U$1") (pin "G6") (pinfunction "DRDY/INT2_G6") (pintype "bidirectional"))
    )
    (net (code "115") (name "unconnected-(U$1-INT1-PadG7)") (class "Default")
      (node (ref "U$1") (pin "G7") (pinfunction "INT1_G7") (pintype "bidirectional"))
    )
    (net (code "116") (name "unconnected-(U$2-VREF-PadG7)") (class "Default")
      (node (ref "U$2") (pin "G7") (pinfunction "VREF_G7") (pintype "bidirectional"))
    )
    (net (code "117") (name "unconnected-(U$4-DRDY{slash}INT2-PadG6)") (class "Default")
      (node (ref "U$4") (pin "G6") (pinfunction "DRDY/INT2_G6") (pintype "bidirectional"))
    )
    (net (code "118") (name "unconnected-(U$4-INT1-PadG7)") (class "Default")
      (node (ref "U$4") (pin "G7") (pinfunction "INT1_G7") (pintype "bidirectional"))
    )
    (net (code "119") (name "unconnected-(U$5-VREF-PadG7)") (class "Default")
      (node (ref "U$5") (pin "G7") (pinfunction "VREF_G7") (pintype "bidirectional"))
    )
    (net (code "120") (name "unconnected-(U1-AUX_ADC-Pad13)") (class "Default")
      (node (ref "U1") (pin "13") (pinfunction "AUX_ADC_13") (pintype "passive"))
    )
    (net (code "121") (name "unconnected-(U1-AUX_DAC-Pad12)") (class "Default")
      (node (ref "U1") (pin "12") (pinfunction "AUX_DAC_12") (pintype "passive"))
    )
    (net (code "122") (name "unconnected-(U1-DIO1-Pad5)") (class "Default")
      (node (ref "U1") (pin "5") (pinfunction "DIO1_5") (pintype "passive"))
    )
    (net (code "123") (name "unconnected-(U1-DIO2-Pad6)") (class "Default")
      (node (ref "U1") (pin "6") (pinfunction "DIO2_6") (pintype "passive"))
    )
    (net (code "124") (name "unconnected-(U1-DNC-Pad11)") (class "Default")
      (node (ref "U1") (pin "11") (pinfunction "DNC_11") (pintype "passive"))
    )
    (net (code "125") (name "unconnected-(U1-DNC_2-Pad8)") (class "Default")
      (node (ref "U1") (pin "8") (pinfunction "DNC_2_8") (pintype "passive"))
    )
    (net (code "126") (name "unconnected-(U1-DNC_3-Pad9)") (class "Default")
      (node (ref "U1") (pin "9") (pinfunction "DNC_3_9") (pintype "passive"))
    )
    (net (code "127") (name "unconnected-(U1-DNC_4-Pad10)") (class "Default")
      (node (ref "U1") (pin "10") (pinfunction "DNC_4_10") (pintype "passive"))
    )
    (net (code "128") (name "unconnected-(U1-FILT-Pad15)") (class "Default")
      (node (ref "U1") (pin "15") (pinfunction "FILT_15") (pintype "passive"))
    )
    (net (code "129") (name "unconnected-(U1-RATE-Pad14)") (class "Default")
      (node (ref "U1") (pin "14") (pinfunction "RATE_14") (pintype "passive"))
    )
    (net (code "130") (name "unconnected-(U1-VREF-Pad20)") (class "Default")
      (node (ref "U1") (pin "20") (pinfunction "VREF_20") (pintype "passive"))
    )
    (net (code "131") (name "unconnected-(U3-NC-PadD1)") (class "Default")
      (node (ref "U3") (pin "D1") (pinfunction "NC_D1") (pintype "passive"))
    )
    (net (code "132") (name "unconnected-(U3-NC_2-PadD2)") (class "Default")
      (node (ref "U3") (pin "D2") (pinfunction "NC_2_D2") (pintype "passive"))
    )
    (net (code "133") (name "unconnected-(U4-NC-PadD1)") (class "Default")
      (node (ref "U4") (pin "D1") (pinfunction "NC_D1") (pintype "passive"))
    )
    (net (code "134") (name "unconnected-(U4-NC_2-PadD2)") (class "Default")
      (node (ref "U4") (pin "D2") (pinfunction "NC_2_D2") (pintype "passive"))
    )
    (net (code "135") (name "unconnected-(U5-INT1-Pad7)") (class "Default")
      (node (ref "U5") (pin "7") (pinfunction "INT1_7") (pintype "bidirectional"))
    )
    (net (code "136") (name "unconnected-(U5-INT2-Pad6)") (class "Default")
      (node (ref "U5") (pin "6") (pinfunction "INT2_6") (pintype "bidirectional"))
    )
    (net (code "137") (name "unconnected-(U6-NC-PadD1)") (class "Default")
      (node (ref "U6") (pin "D1") (pinfunction "NC_D1") (pintype "passive"))
    )
    (net (code "138") (name "unconnected-(U6-NC_2-PadD2)") (class "Default")
      (node (ref "U6") (pin "D2") (pinfunction "NC_2_D2") (pintype "passive"))
    )
    (net (code "139") (name "unconnected-(U7-NC-PadD1)") (class "Default")
      (node (ref "U7") (pin "D1") (pinfunction "NC_D1") (pintype "passive"))
    )
    (net (code "140") (name "unconnected-(U7-NC_2-PadD2)") (class "Default")
      (node (ref "U7") (pin "D2") (pinfunction "NC_2_D2") (pintype "passive"))
    )
    (net (code "141") (name "unconnected-(U8-AUX_CL-Pad7)") (class "Default")
      (node (ref "U8") (pin "7") (pinfunction "AUX_CL_7") (pintype "bidirectional"))
    )
    (net (code "142") (name "unconnected-(U8-AUX_DA-Pad6)") (class "Default")
      (node (ref "U8") (pin "6") (pinfunction "AUX_DA_6") (pintype "bidirectional"))
    )
    (net (code "143") (name "unconnected-(U8-INT-Pad12)") (class "Default")
      (node (ref "U8") (pin "12") (pinfunction "INT_12") (pintype "bidirectional"))
    )
    (net (code "144") (name "unconnected-(U9-PD2(INT0)-Pad32)") (class "Default")
      (node (ref "U9") (pin "32") (pinfunction "PD2(INT0)_32") (pintype "bidirectional"))
    )
    (net (code "145") (name "unconnected-(U9-PD3(INT1)-Pad1)") (class "Default")
      (node (ref "U9") (pin "1") (pinfunction "PD3(INT1)_1") (pintype "bidirectional"))
    )
    (net (code "146") (name "unconnected-(U9-PD4(XCK{slash}T0)-Pad2)") (class "Default")
      (node (ref "U9") (pin "2") (pinfunction "PD4(XCK/T0)_2") (pintype "bidirectional"))
    )
    (net (code "147") (name "unconnected-(U9-PD5(T1)-Pad9)") (class "Default")
      (node (ref "U9") (pin "9") (pinfunction "PD5(T1)_9") (pintype "bidirectional"))
    )
    (net (code "148") (name "unconnected-(U9-PD6(AIN0)-Pad10)") (class "Default")
      (node (ref "U9") (pin "10") (pinfunction "PD6(AIN0)_10") (pintype "bidirectional"))
    )
    (net (code "149") (name "unconnected-(U9-PD7(AIN1)-Pad11)") (class "Default")
      (node (ref "U9") (pin "11") (pinfunction "PD7(AIN1)_11") (pintype "bidirectional"))
    )
    (net (code "150") (name "unconnected-(U10-BP-Pad4)") (class "Default")
      (node (ref "U10") (pin "4") (pinfunction "BP_4") (pintype "input"))
    )
    (net (code "151") (name "~{CS_ADC1}") (class "Default")
      (node (ref "IC1") (pin "18") (pinfunction "~{CS}_18") (pintype "input"))
      (node (ref "SV1") (pin "3") (pinfunction "3_3") (pintype "passive"))
      (node (ref "U9") (pin "25") (pinfunction "PC2(ADC2)_25") (pintype "bidirectional"))
    )
    (net (code "152") (name "~{CS_ADC2}") (class "Default")
      (node (ref "IC2") (pin "18") (pinfunction "~{CS}_18") (pintype "input"))
      (node (ref "SV1") (pin "4") (pinfunction "4_4") (pintype "passive"))
      (node (ref "U9") (pin "26") (pinfunction "PC3(ADC3)_26") (pintype "bidirectional"))
    )
    (net (code "153") (name "~{CS_ADIS}") (class "Default")
      (node (ref "SV1") (pin "1") (pinfunction "1_1") (pintype "passive"))
      (node (ref "U1") (pin "4") (pinfunction "*CS_4") (pintype "passive"))
      (node (ref "U9") (pin "23") (pinfunction "PC0(ADC0)_23") (pintype "bidirectional"))
    )
    (net (code "154") (name "~{CS_ADXRS}") (class "Default")
      (node (ref "SV1") (pin "2") (pinfunction "2_2") (pintype "passive"))
      (node (ref "U2") (pin "4") (pinfunction "*CS_4") (pintype "passive"))
      (node (ref "U9") (pin "24") (pinfunction "PC1(ADC1)_24") (pintype "bidirectional"))
    )
  )
)
